# Motor_Test_Bench_ONE_LAYER.net
KiCad netlist of a schematic drawn in EAGLE
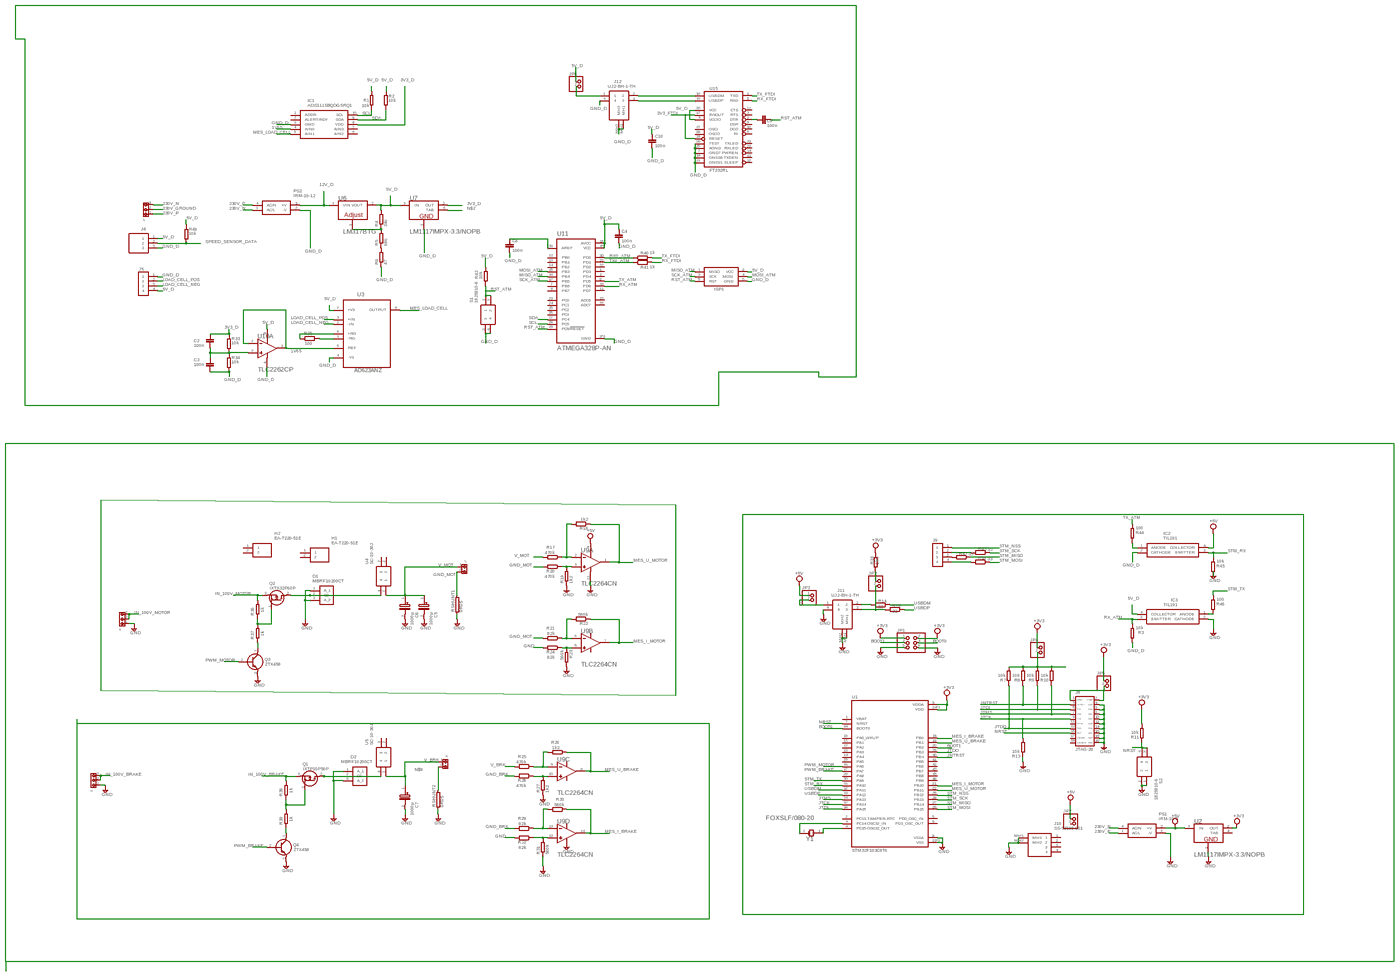
[diagram p0: schematic, sheet 1, overview]
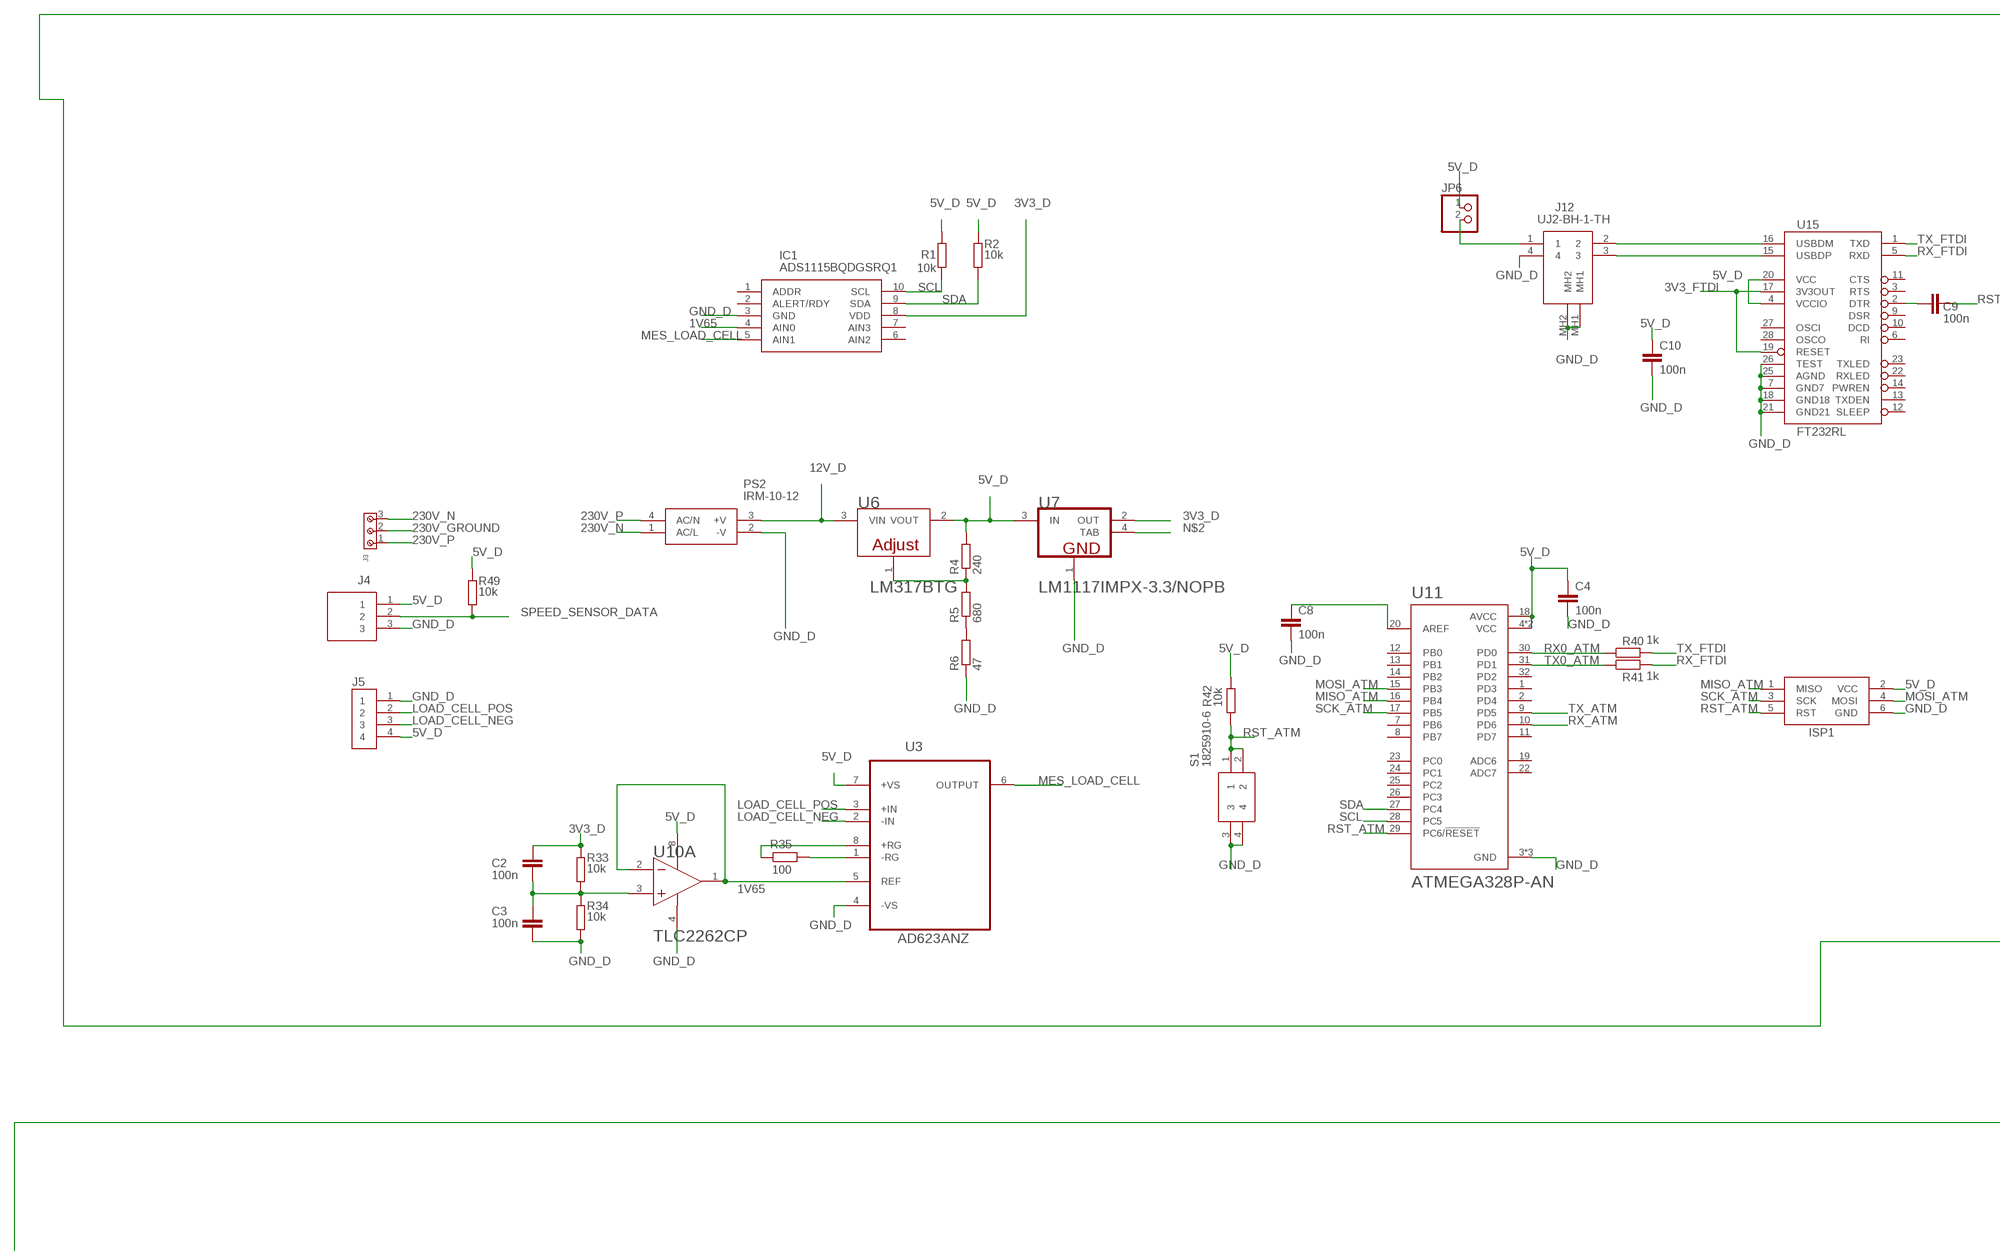
[diagram p1: schematic, sheet 1, part 1 of 4]
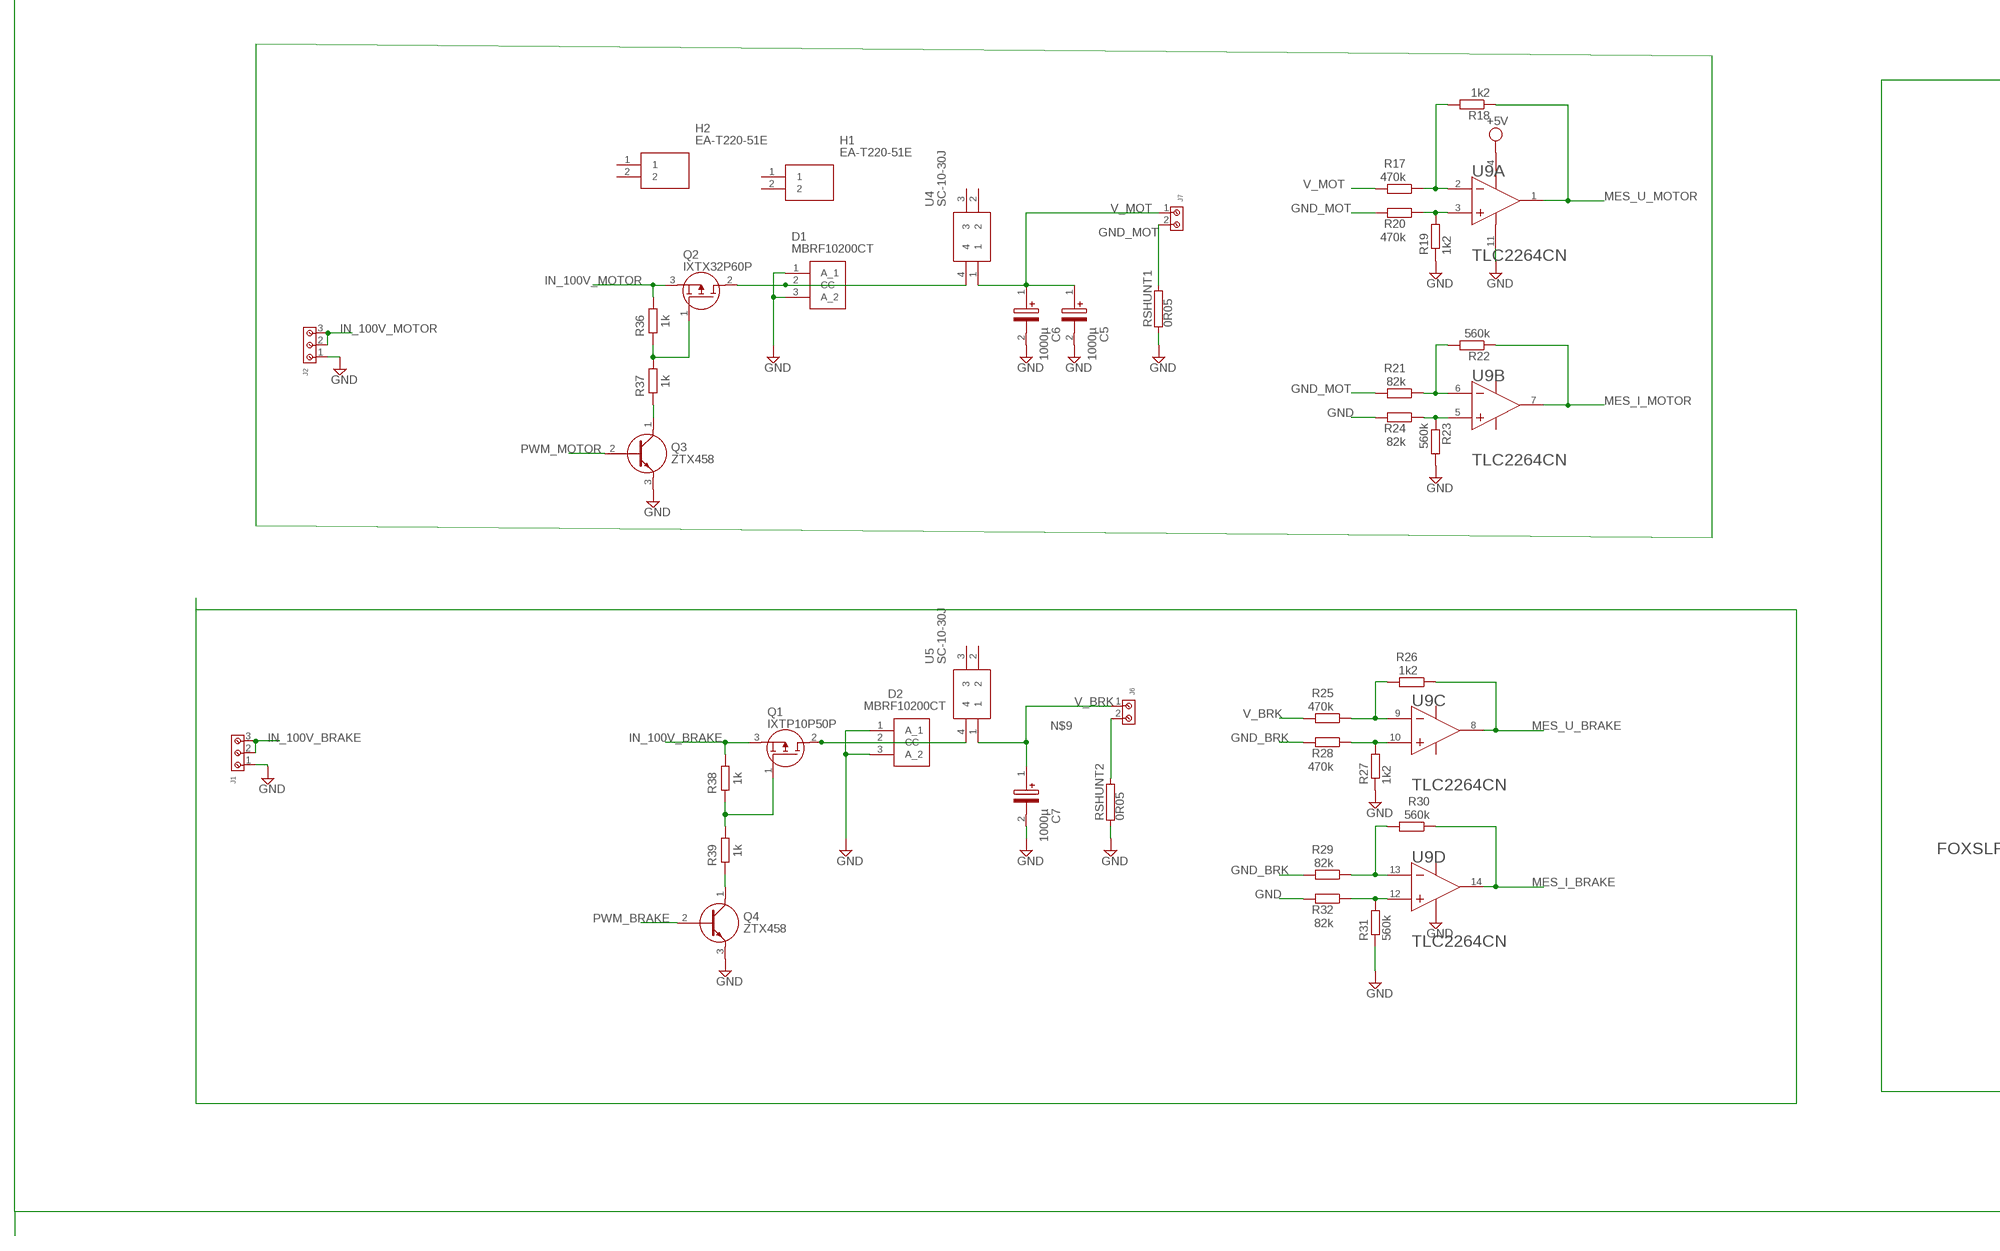
[diagram p2: schematic, sheet 1, part 2 of 4]
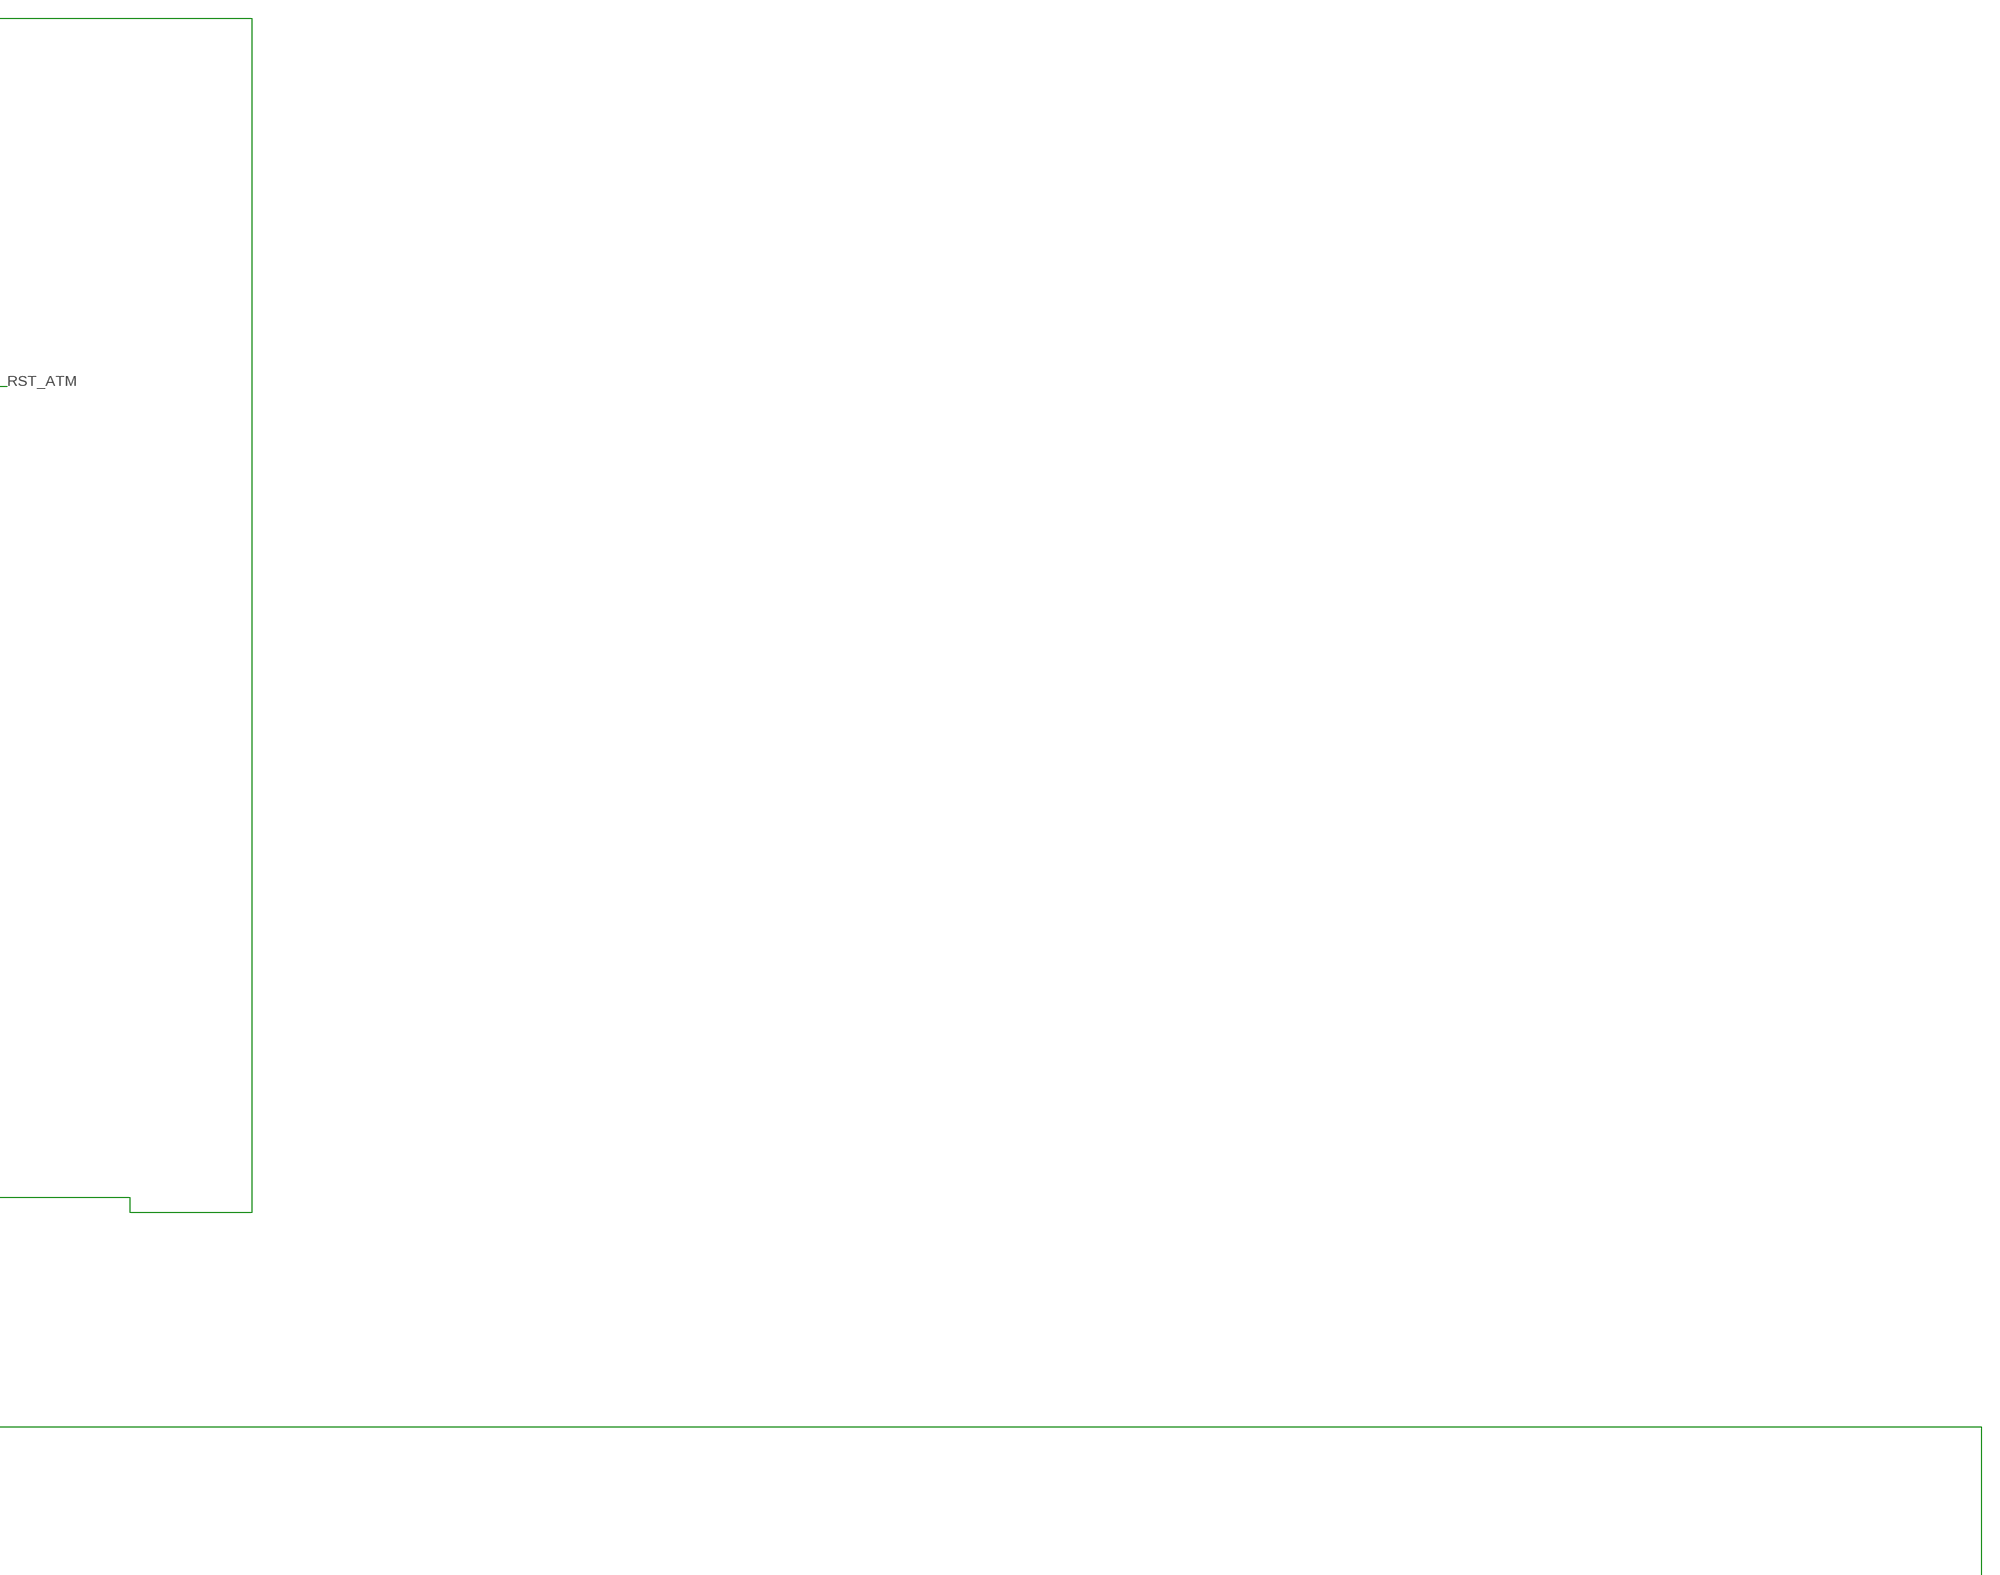
[diagram p3: schematic, sheet 1, part 3 of 4]
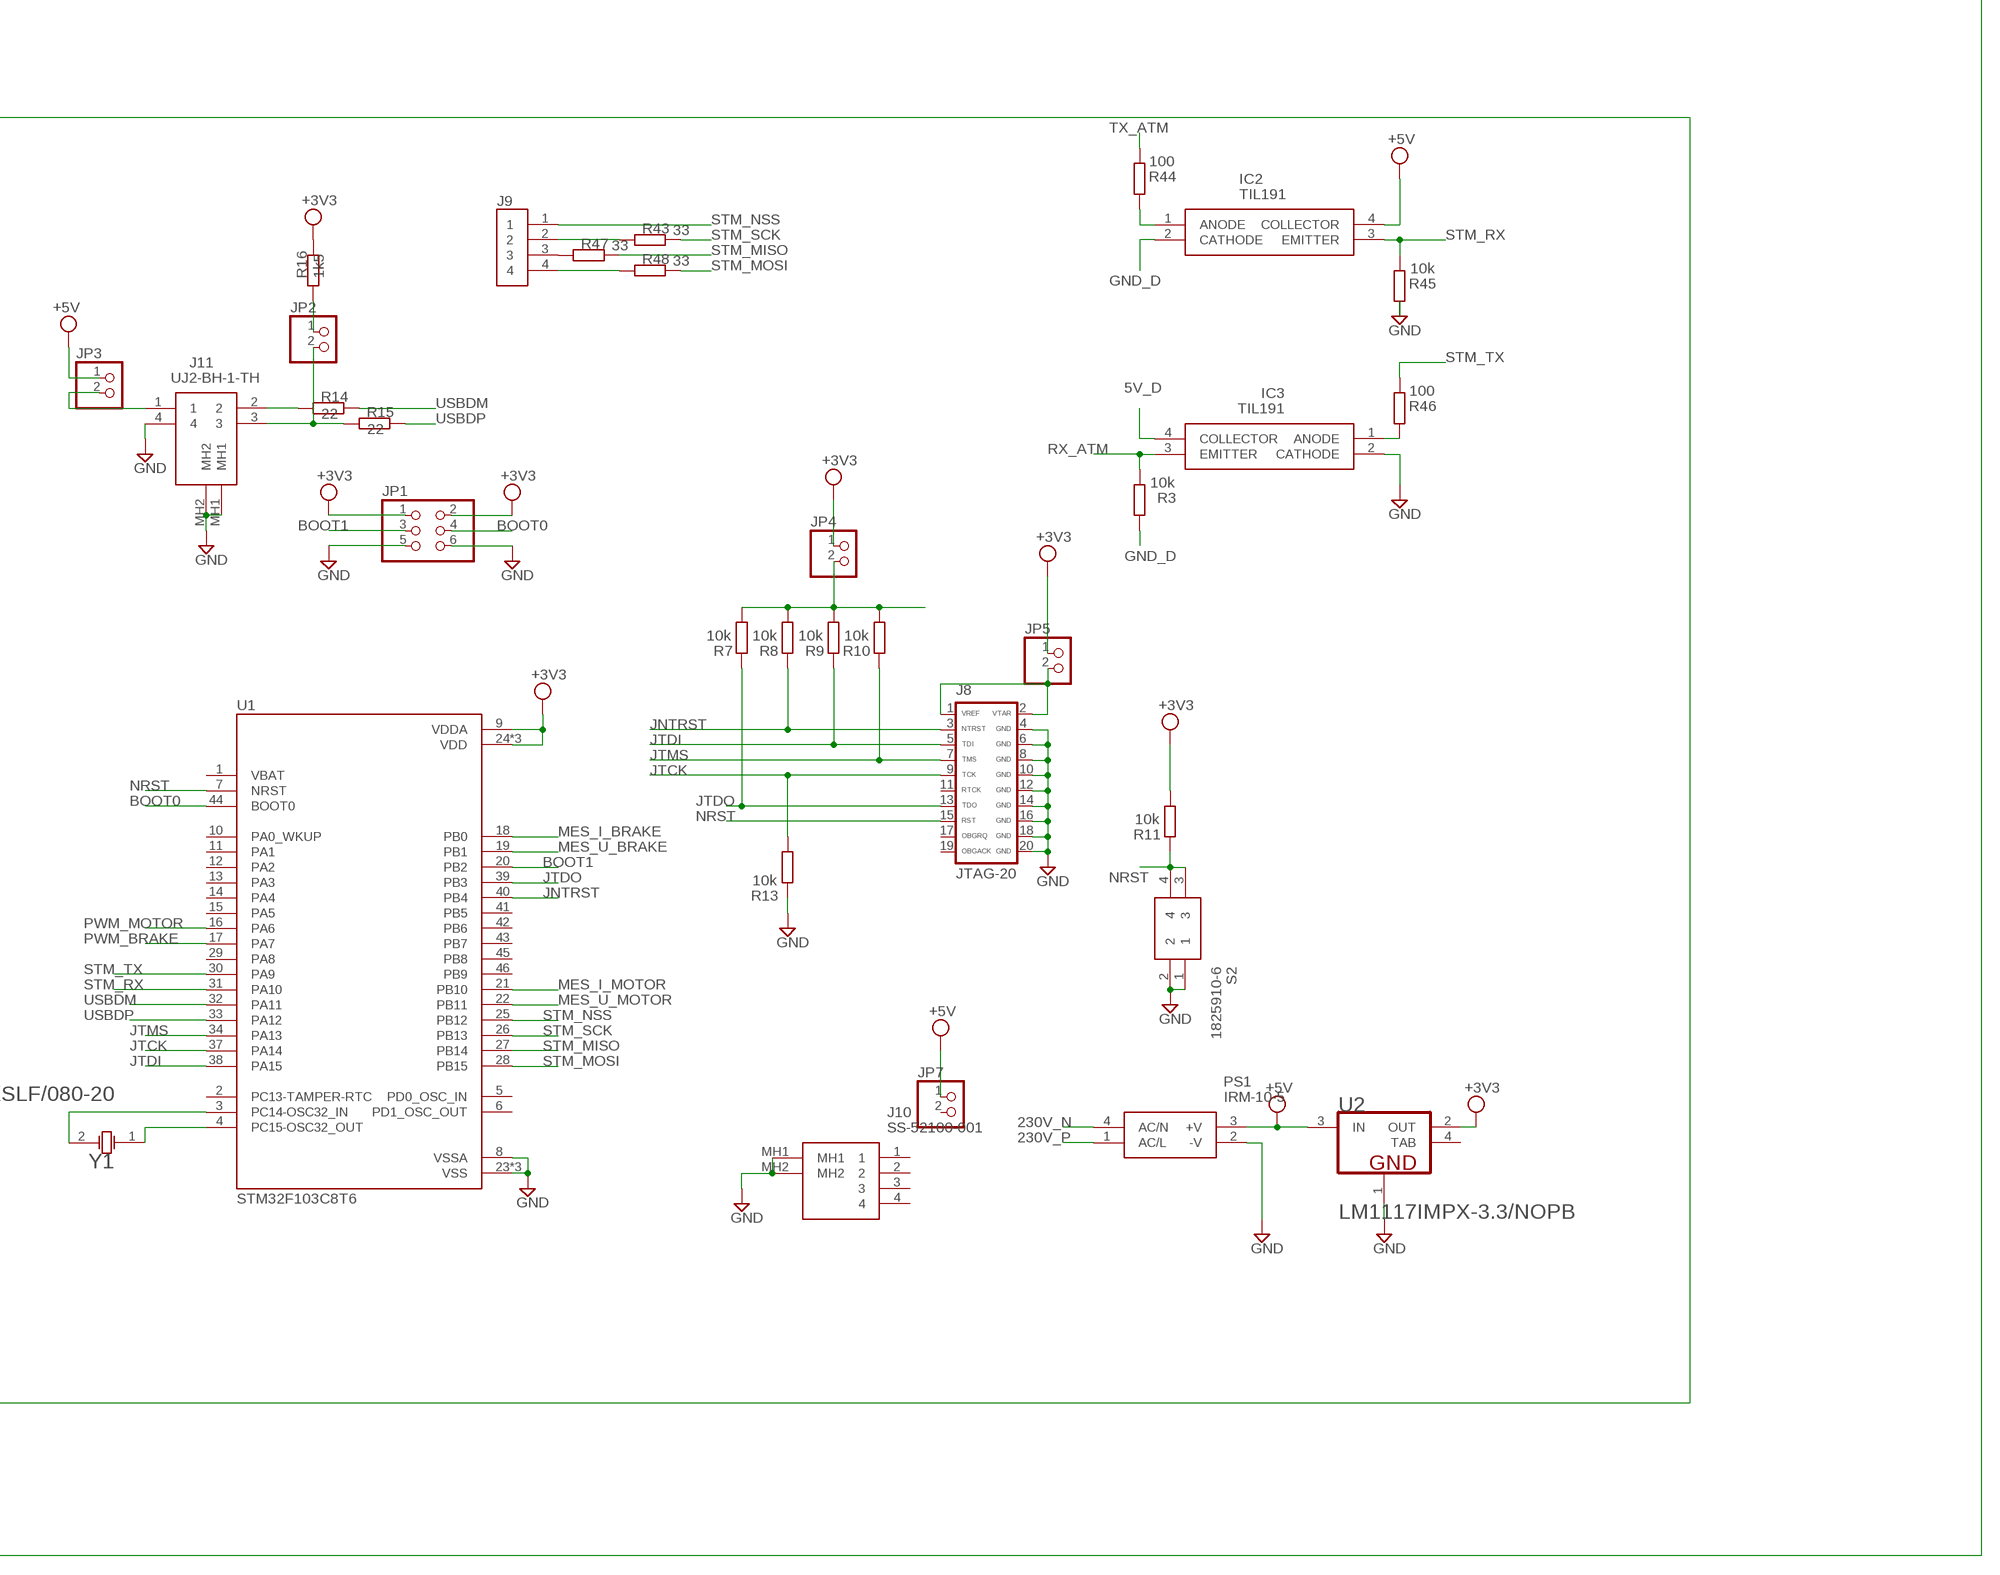
[diagram p4: schematic, sheet 1, part 4 of 4]

(export (version "E")
  (design (tool "Eeschema 10.0.6"))
  (components
    (comp (ref "C2")
      (value "100n")
      (footprint "eagle-import:C0805")
      (libsource (lib "eagle-import") (part "C-EUC0805"))
    )
    (comp (ref "C3")
      (value "100n")
      (footprint "eagle-import:C0805")
      (libsource (lib "eagle-import") (part "C-EUC0805"))
    )
    (comp (ref "C4")
      (value "100n")
      (footprint "eagle-import:CAP_0805")
      (fields
        (field (name "DIGIKEY_PART_NUMBER") "311-1140-2-ND")
        (field (name "MANUFACTURER") "Yageo")
        (field (name "MPN") "CC0805KRX7R9BB104")
        (field (name "CREATED_BY") "PCBLayout.com")
      )
      (libsource (lib "eagle-import") (part "CC0805KRX7R9BB104"))
    )
    (comp (ref "C5")
      (value "1000µ")
      (footprint "eagle-import:SLPX102M200C4P3")
      (fields
        (field (name "MANUFACTURER_PART_NUMBER") "SLPX102M200C4P3")
        (field (name "RS_PART_NUMBER") "7441199P")
      )
      (libsource (lib "eagle-import") (part "SLPX102M200C4P3"))
    )
    (comp (ref "C6")
      (value "1000µ")
      (footprint "eagle-import:SLPX102M200C4P3")
      (fields
        (field (name "MANUFACTURER_PART_NUMBER") "SLPX102M200C4P3")
        (field (name "RS_PART_NUMBER") "7441199P")
      )
      (libsource (lib "eagle-import") (part "SLPX102M200C4P3"))
    )
    (comp (ref "C7")
      (value "1000µ")
      (footprint "eagle-import:SLPX102M200C4P3")
      (fields
        (field (name "MANUFACTURER_PART_NUMBER") "SLPX102M200C4P3")
        (field (name "RS_PART_NUMBER") "7441199P")
      )
      (libsource (lib "eagle-import") (part "SLPX102M200C4P3"))
    )
    (comp (ref "C8")
      (value "100n")
      (footprint "eagle-import:CAP_0805")
      (fields
        (field (name "DIGIKEY_PART_NUMBER") "311-1140-2-ND")
        (field (name "MANUFACTURER") "Yageo")
        (field (name "MPN") "CC0805KRX7R9BB104")
        (field (name "CREATED_BY") "PCBLayout.com")
      )
      (libsource (lib "eagle-import") (part "CC0805KRX7R9BB104"))
    )
    (comp (ref "C9")
      (value "100n")
      (footprint "eagle-import:CAP_0805")
      (fields
        (field (name "DIGIKEY_PART_NUMBER") "311-1140-2-ND")
        (field (name "MANUFACTURER") "Yageo")
        (field (name "MPN") "CC0805KRX7R9BB104")
        (field (name "CREATED_BY") "PCBLayout.com")
      )
      (libsource (lib "eagle-import") (part "CC0805KRX7R9BB104"))
    )
    (comp (ref "C10")
      (value "100n")
      (footprint "eagle-import:CAP_0805")
      (fields
        (field (name "DIGIKEY_PART_NUMBER") "311-1140-2-ND")
        (field (name "MANUFACTURER") "Yageo")
        (field (name "MPN") "CC0805KRX7R9BB104")
        (field (name "CREATED_BY") "PCBLayout.com")
      )
      (libsource (lib "eagle-import") (part "CC0805KRX7R9BB104"))
    )
    (comp (ref "D1")
      (value "MBRF10200CT")
      (footprint "eagle-import:TO254P490X1000X2143-3P")
      (fields (field (name "MOUSER_PART_NUMBER") "621-MBRF10200CT"))
      (libsource (lib "eagle-import") (part "MBRF10200CT"))
    )
    (comp (ref "D2")
      (value "MBRF10200CT")
      (footprint "eagle-import:TO254P490X1000X2143-3P")
      (fields (field (name "MOUSER_PART_NUMBER") "621-MBRF10200CT"))
      (libsource (lib "eagle-import") (part "MBRF10200CT"))
    )
    (comp (ref "H1")
      (value "EA-T220-51E")
      (footprint "eagle-import:EAT22051E")
      (fields (field (name "MOUSER_PART_NUMBER") "588-EA-T220-51E"))
      (libsource (lib "eagle-import") (part "EA-T220-51E"))
    )
    (comp (ref "H2")
      (value "EA-T220-51E")
      (footprint "eagle-import:EAT22051E")
      (fields (field (name "MOUSER_PART_NUMBER") "588-EA-T220-51E"))
      (libsource (lib "eagle-import") (part "EA-T220-51E"))
    )
    (comp (ref "IC1")
      (value "ADS1115BQDGSRQ1")
      (footprint "eagle-import:SOP50P490X110-10N")
      (fields (field (name "MOUSER_PART_NUMBER") "595-ADS1115BQDGSRQ1"))
      (libsource (lib "eagle-import") (part "ADS1115BQDGSRQ1"))
    )
    (comp (ref "IC2")
      (value "TIL191")
      (footprint "eagle-import:DIP762W58P254L450H584Q4N")
      (libsource (lib "eagle-import") (part "TIL191"))
    )
    (comp (ref "IC3")
      (value "TIL191")
      (footprint "eagle-import:DIP762W58P254L450H584Q4N")
      (libsource (lib "eagle-import") (part "TIL191"))
    )
    (comp (ref "ISP1")
      (value "AVRISP-6")
      (footprint "eagle-import:AVRISP")
      (libsource (lib "eagle-import") (part "AVRISP-6"))
    )
    (comp (ref "J1")
      (value "691210910003")
      (footprint "eagle-import:691210910003")
      (libsource (lib "eagle-import") (part "691210910003"))
    )
    (comp (ref "J2")
      (value "691210910003")
      (footprint "eagle-import:691210910003")
      (libsource (lib "eagle-import") (part "691210910003"))
    )
    (comp (ref "J3")
      (value "691210910003")
      (footprint "eagle-import:691210910003")
      (libsource (lib "eagle-import") (part "691210910003"))
    )
    (comp (ref "J4")
      (value "B3B-XH-A(LF)(SN)")
      (footprint "eagle-import:SHDR3W64P0X250_1X3_990X575X700")
      (libsource (lib "eagle-import") (part "B3B-XH-A(LF)(SN)"))
    )
    (comp (ref "J5")
      (value "B4B-XH-A(LF)(SN)")
      (footprint "eagle-import:JST_B4B-XH-A(LF)(SN)")
      (fields (field (name "MF") "JST Sales") (field (name "MP") "B4B-XH-A_LF__SN_"))
      (libsource (lib "eagle-import") (part "B4B-XH-A(LF)(SN)"))
    )
    (comp (ref "J6")
      (value "691210910002")
      (footprint "eagle-import:691210910002")
      (libsource (lib "eagle-import") (part "691210910002"))
    )
    (comp (ref "J7")
      (value "691210910002")
      (footprint "eagle-import:691210910002")
      (libsource (lib "eagle-import") (part "691210910002"))
    )
    (comp (ref "J8")
      (value "JTAG-20")
      (footprint "eagle-import:JTAG-20")
      (libsource (lib "eagle-import") (part "JTAG-20"))
    )
    (comp (ref "J9")
      (value "B4B-XH-A(LF)(SN)")
      (footprint "eagle-import:JST_B4B-XH-A(LF)(SN)")
      (fields (field (name "MF") "JST Sales") (field (name "MP") "B4B-XH-A_LF__SN_"))
      (libsource (lib "eagle-import") (part "B4B-XH-A(LF)(SN)"))
    )
    (comp (ref "J10")
      (value "SS-52100-001")
      (footprint "eagle-import:SS52100001")
      (fields (field (name "MOUSER_PART_NUMBER") "530-SS-52100-001"))
      (libsource (lib "eagle-import") (part "SS-52100-001"))
    )
    (comp (ref "J11")
      (value "UJ2-BH-1-TH")
      (footprint "eagle-import:UJ2BH1TH")
      (fields (field (name "MOUSER_PART_NUMBER") "490-UJ2-BH-1-TH"))
      (libsource (lib "eagle-import") (part "UJ2-BH-1-TH"))
    )
    (comp (ref "J12")
      (value "UJ2-BH-1-TH")
      (footprint "eagle-import:UJ2BH1TH")
      (fields (field (name "MOUSER_PART_NUMBER") "490-UJ2-BH-1-TH"))
      (libsource (lib "eagle-import") (part "UJ2-BH-1-TH"))
    )
    (comp (ref "JP1")
      (value "PINHD-2X3")
      (footprint "eagle-import:2X03")
      (libsource (lib "eagle-import") (part "PINHD-2X3"))
    )
    (comp (ref "JP2")
      (value "PINHD-1X2")
      (footprint "eagle-import:1X02")
      (libsource (lib "eagle-import") (part "PINHD-1X2"))
    )
    (comp (ref "JP3")
      (value "PINHD-1X2")
      (footprint "eagle-import:1X02")
      (libsource (lib "eagle-import") (part "PINHD-1X2"))
    )
    (comp (ref "JP4")
      (value "PINHD-1X2")
      (footprint "eagle-import:1X02")
      (libsource (lib "eagle-import") (part "PINHD-1X2"))
    )
    (comp (ref "JP5")
      (value "PINHD-1X2")
      (footprint "eagle-import:1X02")
      (libsource (lib "eagle-import") (part "PINHD-1X2"))
    )
    (comp (ref "JP6")
      (value "PINHD-1X2")
      (footprint "eagle-import:1X02")
      (libsource (lib "eagle-import") (part "PINHD-1X2"))
    )
    (comp (ref "JP7")
      (value "PINHD-1X2")
      (footprint "eagle-import:1X02")
      (libsource (lib "eagle-import") (part "PINHD-1X2"))
    )
    (comp (ref "PS1")
      (value "IRM-10-5")
      (footprint "eagle-import:IRM-10")
      (fields (field (name "RS_PART_NUMBER") "1358929"))
      (libsource (lib "eagle-import") (part "IRM-10-5"))
    )
    (comp (ref "PS2")
      (value "IRM-10-12")
      (footprint "eagle-import:IRM-10")
      (fields (field (name "RS_PART_NUMBER") "1358930"))
      (libsource (lib "eagle-import") (part "IRM-10-12"))
    )
    (comp (ref "Q1")
      (value "IXTP10P50P")
      (footprint "eagle-import:TO254P483X1028X1700-3P")
      (fields (field (name "MOUSER_PART_NUMBER") "747-IXTP10P50P"))
      (libsource (lib "eagle-import") (part "IXTP10P50P"))
    )
    (comp (ref "Q2")
      (value "IXTX32P60P")
      (footprint "eagle-import:TO545P521X1594X2566-3P")
      (fields (field (name "MOUSER_PART_NUMBER") "747-IXTX32P60P"))
      (libsource (lib "eagle-import") (part "IXTX32P60P"))
    )
    (comp (ref "Q3")
      (value "ZTX458")
      (footprint "eagle-import:ZTX458")
      (fields (field (name "MOUSER_PART_NUMBER") "522-ZTX458"))
      (libsource (lib "eagle-import") (part "ZTX458"))
    )
    (comp (ref "Q4")
      (value "ZTX458")
      (footprint "eagle-import:ZTX458")
      (fields (field (name "MOUSER_PART_NUMBER") "522-ZTX458"))
      (libsource (lib "eagle-import") (part "ZTX458"))
    )
    (comp (ref "R1")
      (value "10k")
      (footprint "eagle-import:R0805")
      (libsource (lib "eagle-import") (part "R-EU_R0805"))
    )
    (comp (ref "R2")
      (value "10k")
      (footprint "eagle-import:R0805")
      (libsource (lib "eagle-import") (part "R-EU_R0805"))
    )
    (comp (ref "R3")
      (value "10k")
      (footprint "eagle-import:R0805")
      (libsource (lib "eagle-import") (part "R-EU_R0805"))
    )
    (comp (ref "R4")
      (value "240")
      (footprint "eagle-import:R0805")
      (libsource (lib "eagle-import") (part "R-EU_R0805"))
    )
    (comp (ref "R5")
      (value "680")
      (footprint "eagle-import:R0805")
      (libsource (lib "eagle-import") (part "R-EU_R0805"))
    )
    (comp (ref "R6")
      (value "47")
      (footprint "eagle-import:R0805")
      (libsource (lib "eagle-import") (part "R-EU_R0805"))
    )
    (comp (ref "R7")
      (value "10k")
      (footprint "eagle-import:R0805")
      (libsource (lib "eagle-import") (part "R-EU_R0805"))
    )
    (comp (ref "R8")
      (value "10k")
      (footprint "eagle-import:R0805")
      (libsource (lib "eagle-import") (part "R-EU_R0805"))
    )
    (comp (ref "R9")
      (value "10k")
      (footprint "eagle-import:R0805")
      (libsource (lib "eagle-import") (part "R-EU_R0805"))
    )
    (comp (ref "R10")
      (value "10k")
      (footprint "eagle-import:R0805")
      (libsource (lib "eagle-import") (part "R-EU_R0805"))
    )
    (comp (ref "R11")
      (value "10k")
      (footprint "eagle-import:R0805")
      (libsource (lib "eagle-import") (part "R-EU_R0805"))
    )
    (comp (ref "R13")
      (value "10k")
      (footprint "eagle-import:R0805")
      (libsource (lib "eagle-import") (part "R-EU_R0805"))
    )
    (comp (ref "R14")
      (value "22")
      (footprint "eagle-import:R0805")
      (libsource (lib "eagle-import") (part "R-EU_R0805"))
    )
    (comp (ref "R15")
      (value "22")
      (footprint "eagle-import:R0805")
      (libsource (lib "eagle-import") (part "R-EU_R0805"))
    )
    (comp (ref "R16")
      (value "1k5")
      (footprint "eagle-import:R0805")
      (libsource (lib "eagle-import") (part "R-EU_R0805"))
    )
    (comp (ref "R17")
      (value "470k")
      (footprint "eagle-import:R0805")
      (libsource (lib "eagle-import") (part "R-EU_R0805"))
    )
    (comp (ref "R18")
      (value "1k2")
      (footprint "eagle-import:R0805")
      (libsource (lib "eagle-import") (part "R-EU_R0805"))
    )
    (comp (ref "R19")
      (value "1k2")
      (footprint "eagle-import:R0805")
      (libsource (lib "eagle-import") (part "R-EU_R0805"))
    )
    (comp (ref "R20")
      (value "470k")
      (footprint "eagle-import:R0805")
      (libsource (lib "eagle-import") (part "R-EU_R0805"))
    )
    (comp (ref "R21")
      (value "82k")
      (footprint "eagle-import:R0805")
      (libsource (lib "eagle-import") (part "R-EU_R0805"))
    )
    (comp (ref "R22")
      (value "560k")
      (footprint "eagle-import:R0805")
      (libsource (lib "eagle-import") (part "R-EU_R0805"))
    )
    (comp (ref "R23")
      (value "560k")
      (footprint "eagle-import:R0805")
      (libsource (lib "eagle-import") (part "R-EU_R0805"))
    )
    (comp (ref "R24")
      (value "82k")
      (footprint "eagle-import:R0805")
      (libsource (lib "eagle-import") (part "R-EU_R0805"))
    )
    (comp (ref "R25")
      (value "470k")
      (footprint "eagle-import:R0805")
      (libsource (lib "eagle-import") (part "R-EU_R0805"))
    )
    (comp (ref "R26")
      (value "1k2")
      (footprint "eagle-import:R0805")
      (libsource (lib "eagle-import") (part "R-EU_R0805"))
    )
    (comp (ref "R27")
      (value "1k2")
      (footprint "eagle-import:R0805")
      (libsource (lib "eagle-import") (part "R-EU_R0805"))
    )
    (comp (ref "R28")
      (value "470k")
      (footprint "eagle-import:R0805")
      (libsource (lib "eagle-import") (part "R-EU_R0805"))
    )
    (comp (ref "R29")
      (value "82k")
      (footprint "eagle-import:R0805")
      (libsource (lib "eagle-import") (part "R-EU_R0805"))
    )
    (comp (ref "R30")
      (value "560k")
      (footprint "eagle-import:R0805")
      (libsource (lib "eagle-import") (part "R-EU_R0805"))
    )
    (comp (ref "R31")
      (value "560k")
      (footprint "eagle-import:R0805")
      (libsource (lib "eagle-import") (part "R-EU_R0805"))
    )
    (comp (ref "R32")
      (value "82k")
      (footprint "eagle-import:R0805")
      (libsource (lib "eagle-import") (part "R-EU_R0805"))
    )
    (comp (ref "R33")
      (value "10k")
      (footprint "eagle-import:R0805")
      (libsource (lib "eagle-import") (part "R-EU_R0805"))
    )
    (comp (ref "R34")
      (value "10k")
      (footprint "eagle-import:R0805")
      (libsource (lib "eagle-import") (part "R-EU_R0805"))
    )
    (comp (ref "R35")
      (value "100")
      (footprint "eagle-import:R0805")
      (libsource (lib "eagle-import") (part "R-EU_R0805"))
    )
    (comp (ref "R36")
      (value "1k")
      (footprint "eagle-import:R0805")
      (libsource (lib "eagle-import") (part "R-EU_R0805"))
    )
    (comp (ref "R37")
      (value "1k")
      (footprint "eagle-import:R0805")
      (libsource (lib "eagle-import") (part "R-EU_R0805"))
    )
    (comp (ref "R38")
      (value "1k")
      (footprint "eagle-import:R0805")
      (libsource (lib "eagle-import") (part "R-EU_R0805"))
    )
    (comp (ref "R39")
      (value "1k")
      (footprint "eagle-import:R0805")
      (libsource (lib "eagle-import") (part "R-EU_R0805"))
    )
    (comp (ref "R40")
      (value "1k")
      (footprint "eagle-import:R0805")
      (libsource (lib "eagle-import") (part "R-EU_R0805"))
    )
    (comp (ref "R41")
      (value "1k")
      (footprint "eagle-import:R0805")
      (libsource (lib "eagle-import") (part "R-EU_R0805"))
    )
    (comp (ref "R42")
      (value "10k")
      (footprint "eagle-import:R0805")
      (libsource (lib "eagle-import") (part "R-EU_R0805"))
    )
    (comp (ref "R43")
      (value "33")
      (footprint "eagle-import:R0805")
      (libsource (lib "eagle-import") (part "R-EU_R0805"))
    )
    (comp (ref "R44")
      (value "100")
      (footprint "eagle-import:R0805")
      (libsource (lib "eagle-import") (part "R-EU_R0805"))
    )
    (comp (ref "R45")
      (value "10k")
      (footprint "eagle-import:R0805")
      (libsource (lib "eagle-import") (part "R-EU_R0805"))
    )
    (comp (ref "R46")
      (value "100")
      (footprint "eagle-import:R0805")
      (libsource (lib "eagle-import") (part "R-EU_R0805"))
    )
    (comp (ref "R47")
      (value "33")
      (footprint "eagle-import:R0805")
      (libsource (lib "eagle-import") (part "R-EU_R0805"))
    )
    (comp (ref "R48")
      (value "33")
      (footprint "eagle-import:R0805")
      (libsource (lib "eagle-import") (part "R-EU_R0805"))
    )
    (comp (ref "R49")
      (value "10k")
      (footprint "eagle-import:R0805")
      (libsource (lib "eagle-import") (part "R-EU_R0805"))
    )
    (comp (ref "RSHUNT1")
      (value "0R05")
      (footprint "eagle-import:RS05_69-70")
      (libsource (lib "eagle-import") (part "RRS05_69-70"))
    )
    (comp (ref "RSHUNT2")
      (value "0R05")
      (footprint "eagle-import:RS05_69-70")
      (libsource (lib "eagle-import") (part "RRS05_69-70"))
    )
    (comp (ref "S1")
      (value "1825910-6")
      (footprint "eagle-import:1825910-6")
      (libsource (lib "eagle-import") (part "1825910-6"))
    )
    (comp (ref "S2")
      (value "1825910-6")
      (footprint "eagle-import:1825910-6")
      (libsource (lib "eagle-import") (part "1825910-6"))
    )
    (comp (ref "U1")
      (value "STM32F103C8T6")
      (footprint "eagle-import:QFP50P900X900X160-48N")
      (fields (field (name "MF") "STMicroelectronics"))
      (libsource (lib "eagle-import") (part "STM32F103C8T6"))
    )
    (comp (ref "U2")
      (value "NATIONAL_SEMICONDUCTOR_LM1117IMPX-3.3-NOPBNATIONAL_SEMICONDUCTOR_LM1117IMPX-3.3-NOPB_0_2")
      (footprint "eagle-import:NATIONAL_SEMICONDUCTOR_LM1117IMPX-3.3-NOPB_2")
      (fields (field (name "MF") "National Semiconductor") (field (name "MPN") "LM1117IMPX-3.3/NOPB"))
      (libsource (lib "eagle-import") (part "NATIONAL_SEMICONDUCTOR_LM1117IMPX-3.3-NOPBNATIONAL_SEMICONDUCTOR_LM1117IMPX-3.3-NOPB_0_2"))
    )
    (comp (ref "U3")
      (value "AD623ANZ")
      (footprint "eagle-import:DIP254P762X533-8")
      (fields (field (name "MF") "Analog Devices"))
      (libsource (lib "eagle-import") (part "AD623ANZ"))
    )
    (comp (ref "U4")
      (value "SC-10-30J")
      (footprint "eagle-import:SC-10-30J")
      (fields (field (name "MOUSER_PART_NUMBER") "80-SC-10-30J") (field (name "RS_PART_NUMBER") "8633778P"))
      (libsource (lib "eagle-import") (part "SC-10-30J"))
    )
    (comp (ref "U5")
      (value "SC-10-30J")
      (footprint "eagle-import:SC-10-30J")
      (fields (field (name "MOUSER_PART_NUMBER") "80-SC-10-30J") (field (name "RS_PART_NUMBER") "8633778P"))
      (libsource (lib "eagle-import") (part "SC-10-30J"))
    )
    (comp (ref "U6")
      (value "ON_SEMI_LM317BTGON_SEMI_LM317BTG_0_0")
      (footprint "eagle-import:ON_SEMI_LM317BTG_0")
      (fields
        (field (name "DIGIKEY_PART_NUMBER") "LM317BTGOS-ND")
        (field (name "MF") "ON Semi")
        (field (name "MOUSER_PART_NUMBER") "863-LM317BTG")
      )
      (libsource (lib "eagle-import") (part "ON_SEMI_LM317BTGON_SEMI_LM317BTG_0_0"))
    )
    (comp (ref "U7")
      (value "NATIONAL_SEMICONDUCTOR_LM1117IMPX-3.3-NOPBNATIONAL_SEMICONDUCTOR_LM1117IMPX-3.3-NOPB_0_2")
      (footprint "eagle-import:NATIONAL_SEMICONDUCTOR_LM1117IMPX-3.3-NOPB_2")
      (fields (field (name "MF") "National Semiconductor") (field (name "MPN") "LM1117IMPX-3.3/NOPB"))
      (libsource (lib "eagle-import") (part "NATIONAL_SEMICONDUCTOR_LM1117IMPX-3.3-NOPBNATIONAL_SEMICONDUCTOR_LM1117IMPX-3.3-NOPB_0_2"))
    )
    (comp (ref "U9")
      (value "TEXAS_INSTRUMENTS_TLC2264CNTEXAS_INSTRUMENTS_TLC2264CN_0_0")
      (footprint "eagle-import:TEXAS_INSTRUMENTS_TLC2264CN_0")
      (fields (field (name "MF") "Texas Instruments") (field (name "MPN") "TLC2264CN"))
      (libsource (lib "eagle-import") (part "TEXAS_INSTRUMENTS_TLC2264CNTEXAS_INSTRUMENTS_TLC2264CN_0_0"))
    )
    (comp (ref "U10")
      (value "TEXAS_INSTRUMENTS_TLC2262CPTEXAS_INSTRUMENTS_TLC2262CP_0_0")
      (footprint "eagle-import:TEXAS_INSTRUMENTS_TLC2262CP_0")
      (fields (field (name "MF") "Texas Instruments") (field (name "MPN") "TLC2262CP"))
      (libsource (lib "eagle-import") (part "TEXAS_INSTRUMENTS_TLC2262CPTEXAS_INSTRUMENTS_TLC2262CP_0_0"))
    )
    (comp (ref "U11")
      (value "ATMEGA328P-AN")
      (footprint "eagle-import:QFP80P900X900X120-32N")
      (fields (field (name "MF") "Microchip"))
      (libsource (lib "eagle-import") (part "ATMEGA328P-AN"))
    )
    (comp (ref "U15")
      (value "FT232RL")
      (footprint "eagle-import:SSOP28DB")
      (libsource (lib "eagle-import") (part "FT232RLSSOP"))
    )
    (comp (ref "Y1")
      (value "FOX_ELECTRONICS_FOXSLF-080-20FOX_ELECTRONICS_FOXSLF-080-20_0_0")
      (footprint "eagle-import:FOX_ELECTRONICS_FOXSLF-080-20_0")
      (fields (field (name "MF") "Fox Electronics") (field (name "MPN") "FOXSLF/080-20"))
      (libsource (lib "eagle-import") (part "FOX_ELECTRONICS_FOXSLF-080-20FOX_ELECTRONICS_FOXSLF-080-20_0_0"))
    )
  )
  (nets
    (net (code "1") (name "+3V3") (class "Default")
      (node (ref "JP1") (pin "1") (pinfunction "1_1") (pintype "passive"))
      (node (ref "JP1") (pin "2") (pinfunction "2_2") (pintype "passive"))
      (node (ref "JP4") (pin "1") (pinfunction "1_1") (pintype "passive"))
      (node (ref "JP5") (pin "1") (pinfunction "1_1") (pintype "passive"))
      (node (ref "R11") (pin "2") (pinfunction "2_2") (pintype "passive"))
      (node (ref "R16") (pin "1") (pinfunction "1_1") (pintype "passive"))
      (node (ref "U1") (pin "24") (pinfunction "VDD_24") (pintype "power_in"))
      (node (ref "U1") (pin "36") (pinfunction "VDD_36") (pintype "power_in"))
      (node (ref "U1") (pin "48") (pinfunction "VDD_48") (pintype "power_in"))
      (node (ref "U1") (pin "9") (pinfunction "VDDA_9") (pintype "power_in"))
      (node (ref "U2") (pin "2") (pinfunction "OUT_2") (pintype "power_in"))
    )
    (net (code "2") (name "+5V") (class "Default")
      (node (ref "IC2") (pin "4") (pinfunction "COLLECTOR_4") (pintype "bidirectional"))
      (node (ref "JP3") (pin "1") (pinfunction "1_1") (pintype "passive"))
      (node (ref "JP7") (pin "1") (pinfunction "1_1") (pintype "passive"))
      (node (ref "PS1") (pin "3") (pinfunction "+V_3") (pintype "bidirectional"))
      (node (ref "U2") (pin "3") (pinfunction "IN_3") (pintype "power_in"))
      (node (ref "U9") (pin "4") (pinfunction "VDD+_4") (pintype "power_in"))
    )
    (net (code "3") (name "/1V65") (class "Default")
      (node (ref "IC1") (pin "4") (pinfunction "AIN0_4") (pintype "bidirectional"))
      (node (ref "U10") (pin "1") (pinfunction "OUT1_1") (pintype "output"))
      (node (ref "U10") (pin "2") (pinfunction "IN1-_2") (pintype "input"))
      (node (ref "U3") (pin "5") (pinfunction "REF_5") (pintype "passive"))
    )
    (net (code "4") (name "/3V3_D") (class "Default")
      (node (ref "C2") (pin "1") (pinfunction "1_1") (pintype "passive"))
      (node (ref "IC1") (pin "8") (pinfunction "VDD_8") (pintype "bidirectional"))
      (node (ref "R33") (pin "1") (pinfunction "1_1") (pintype "passive"))
      (node (ref "U7") (pin "2") (pinfunction "OUT_2") (pintype "power_in"))
    )
    (net (code "5") (name "/3V3_FTDI") (class "Default")
      (node (ref "U15") (pin "17") (pinfunction "3V3OUT_17") (pintype "output"))
      (node (ref "U15") (pin "19") (pinfunction "RESET_19") (pintype "input"))
    )
    (net (code "6") (name "/5V_D") (class "Default")
      (node (ref "C10") (pin "1") (pinfunction "1_1") (pintype "passive"))
      (node (ref "C4") (pin "1") (pinfunction "1_1") (pintype "passive"))
      (node (ref "IC3") (pin "4") (pinfunction "COLLECTOR_4") (pintype "bidirectional"))
      (node (ref "ISP1") (pin "2") (pinfunction "VCC_2") (pintype "power_in"))
      (node (ref "J4") (pin "1") (pinfunction "1_1") (pintype "bidirectional"))
      (node (ref "J5") (pin "4") (pinfunction "4_4") (pintype "passive"))
      (node (ref "JP6") (pin "1") (pinfunction "1_1") (pintype "passive"))
      (node (ref "R1") (pin "2") (pinfunction "2_2") (pintype "passive"))
      (node (ref "R2") (pin "2") (pinfunction "2_2") (pintype "passive"))
      (node (ref "R4") (pin "2") (pinfunction "2_2") (pintype "passive"))
      (node (ref "R42") (pin "2") (pinfunction "2_2") (pintype "passive"))
      (node (ref "R49") (pin "1") (pinfunction "1_1") (pintype "passive"))
      (node (ref "U10") (pin "8") (pinfunction "VDD+_8") (pintype "power_in"))
      (node (ref "U11") (pin "18") (pinfunction "AVCC_18") (pintype "power_in"))
      (node (ref "U11") (pin "4") (pinfunction "VCC_4") (pintype "power_in"))
      (node (ref "U11") (pin "6") (pinfunction "VCC_6") (pintype "power_in"))
      (node (ref "U15") (pin "20") (pinfunction "VCC_20") (pintype "power_in"))
      (node (ref "U15") (pin "4") (pinfunction "VCCIO_4") (pintype "power_in"))
      (node (ref "U3") (pin "7") (pinfunction "+VS_7") (pintype "power_in"))
      (node (ref "U6") (pin "2") (pinfunction "VOUT_2") (pintype "output"))
      (node (ref "U7") (pin "3") (pinfunction "IN_3") (pintype "power_in"))
    )
    (net (code "7") (name "/12V_D") (class "Default")
      (node (ref "PS2") (pin "3") (pinfunction "+V_3") (pintype "bidirectional"))
      (node (ref "U6") (pin "3") (pinfunction "VIN_3") (pintype "input"))
    )
    (net (code "8") (name "/230V_GROUND") (class "Default")
      (node (ref "J3") (pin "2") (pinfunction "2_2") (pintype "passive"))
    )
    (net (code "9") (name "/230V_N") (class "Default")
      (node (ref "J3") (pin "3") (pinfunction "3_3") (pintype "passive"))
      (node (ref "PS1") (pin "4") (pinfunction "AC/N_4") (pintype "bidirectional"))
      (node (ref "PS2") (pin "1") (pinfunction "AC/L_1") (pintype "bidirectional"))
    )
    (net (code "10") (name "/230V_P") (class "Default")
      (node (ref "J3") (pin "1") (pinfunction "1_1") (pintype "passive"))
      (node (ref "PS1") (pin "1") (pinfunction "AC/L_1") (pintype "bidirectional"))
      (node (ref "PS2") (pin "4") (pinfunction "AC/N_4") (pintype "bidirectional"))
    )
    (net (code "11") (name "/BOOT0") (class "Default")
      (node (ref "JP1") (pin "4") (pinfunction "4_4") (pintype "passive"))
      (node (ref "U1") (pin "44") (pinfunction "BOOT0_44") (pintype "input"))
    )
    (net (code "12") (name "/BOOT1") (class "Default")
      (node (ref "JP1") (pin "3") (pinfunction "3_3") (pintype "passive"))
      (node (ref "U1") (pin "20") (pinfunction "PB2_20") (pintype "bidirectional"))
    )
    (net (code "13") (name "/GND_BRK") (class "Default")
      (node (ref "R28") (pin "2") (pinfunction "2_2") (pintype "passive"))
      (node (ref "R29") (pin "2") (pinfunction "2_2") (pintype "passive"))
    )
    (net (code "14") (name "/GND_D") (class "Default")
      (node (ref "C10") (pin "2") (pinfunction "2_2") (pintype "passive"))
      (node (ref "C3") (pin "2") (pinfunction "2_2") (pintype "passive"))
      (node (ref "C4") (pin "2") (pinfunction "2_2") (pintype "passive"))
      (node (ref "C8") (pin "2") (pinfunction "2_2") (pintype "passive"))
      (node (ref "IC1") (pin "3") (pinfunction "GND_3") (pintype "bidirectional"))
      (node (ref "IC2") (pin "2") (pinfunction "CATHODE_2") (pintype "bidirectional"))
      (node (ref "ISP1") (pin "6") (pinfunction "GND_6") (pintype "power_in"))
      (node (ref "J12") (pin "4") (pinfunction "4_4") (pintype "bidirectional"))
      (node (ref "J12") (pin "MH1") (pinfunction "MH1_MH1") (pintype "bidirectional"))
      (node (ref "J12") (pin "MH2") (pinfunction "MH2_MH2") (pintype "bidirectional"))
      (node (ref "J4") (pin "3") (pinfunction "3_3") (pintype "bidirectional"))
      (node (ref "J5") (pin "1") (pinfunction "1_1") (pintype "passive"))
      (node (ref "PS2") (pin "2") (pinfunction "-V_2") (pintype "bidirectional"))
      (node (ref "R3") (pin "1") (pinfunction "1_1") (pintype "passive"))
      (node (ref "R34") (pin "2") (pinfunction "2_2") (pintype "passive"))
      (node (ref "R6") (pin "1") (pinfunction "1_1") (pintype "passive"))
      (node (ref "S1") (pin "3") (pinfunction "3_3") (pintype "bidirectional"))
      (node (ref "S1") (pin "4") (pinfunction "4_4") (pintype "bidirectional"))
      (node (ref "U10") (pin "4") (pinfunction "VDD-/GND_4") (pintype "power_in"))
      (node (ref "U11") (pin "21") (pinfunction "GND_21") (pintype "power_in"))
      (node (ref "U11") (pin "3") (pinfunction "GND_3") (pintype "power_in"))
      (node (ref "U11") (pin "5") (pinfunction "GND_5") (pintype "power_in"))
      (node (ref "U15") (pin "18") (pinfunction "GND18_18") (pintype "power_in"))
      (node (ref "U15") (pin "21") (pinfunction "GND21_21") (pintype "power_in"))
      (node (ref "U15") (pin "25") (pinfunction "AGND_25") (pintype "power_in"))
      (node (ref "U15") (pin "26") (pinfunction "TEST_26") (pintype "input"))
      (node (ref "U15") (pin "7") (pinfunction "GND7_7") (pintype "power_in"))
      (node (ref "U3") (pin "4") (pinfunction "-VS_4") (pintype "power_in"))
      (node (ref "U7") (pin "1") (pinfunction "GND_1") (pintype "power_in"))
    )
    (net (code "15") (name "/GND_MOT") (class "Default")
      (node (ref "J7") (pin "2") (pinfunction "2_2") (pintype "passive"))
      (node (ref "R20") (pin "2") (pinfunction "2_2") (pintype "passive"))
      (node (ref "R21") (pin "2") (pinfunction "2_2") (pintype "passive"))
      (node (ref "RSHUNT1") (pin "2") (pinfunction "2_2") (pintype "passive"))
    )
    (net (code "16") (name "/IN_100V_BRAKE") (class "Default")
      (node (ref "J1") (pin "2") (pinfunction "2_2") (pintype "passive"))
      (node (ref "J1") (pin "3") (pinfunction "3_3") (pintype "passive"))
      (node (ref "Q1") (pin "3") (pinfunction "S_3") (pintype "bidirectional"))
      (node (ref "R38") (pin "2") (pinfunction "2_2") (pintype "passive"))
    )
    (net (code "17") (name "/IN_100V_MOTOR") (class "Default")
      (node (ref "J2") (pin "2") (pinfunction "2_2") (pintype "passive"))
      (node (ref "J2") (pin "3") (pinfunction "3_3") (pintype "passive"))
      (node (ref "Q2") (pin "3") (pinfunction "S_3") (pintype "bidirectional"))
      (node (ref "R36") (pin "2") (pinfunction "2_2") (pintype "passive"))
    )
    (net (code "18") (name "/JNTRST") (class "Default")
      (node (ref "J8") (pin "3") (pinfunction "NTRST_3") (pintype "passive"))
      (node (ref "R8") (pin "1") (pinfunction "1_1") (pintype "passive"))
      (node (ref "U1") (pin "40") (pinfunction "PB4_40") (pintype "bidirectional"))
    )
    (net (code "19") (name "/JTCK") (class "Default")
      (node (ref "J8") (pin "9") (pinfunction "TCK_9") (pintype "passive"))
      (node (ref "R13") (pin "2") (pinfunction "2_2") (pintype "passive"))
      (node (ref "U1") (pin "37") (pinfunction "PA14_37") (pintype "bidirectional"))
    )
    (net (code "20") (name "/JTDI") (class "Default")
      (node (ref "J8") (pin "5") (pinfunction "TDI_5") (pintype "passive"))
      (node (ref "R9") (pin "1") (pinfunction "1_1") (pintype "passive"))
      (node (ref "U1") (pin "38") (pinfunction "PA15_38") (pintype "bidirectional"))
    )
    (net (code "21") (name "/JTDO") (class "Default")
      (node (ref "J8") (pin "13") (pinfunction "TDO_13") (pintype "passive"))
      (node (ref "R7") (pin "1") (pinfunction "1_1") (pintype "passive"))
      (node (ref "U1") (pin "39") (pinfunction "PB3_39") (pintype "bidirectional"))
    )
    (net (code "22") (name "/JTMS") (class "Default")
      (node (ref "J8") (pin "7") (pinfunction "TMS_7") (pintype "passive"))
      (node (ref "R10") (pin "1") (pinfunction "1_1") (pintype "passive"))
      (node (ref "U1") (pin "34") (pinfunction "PA13_34") (pintype "bidirectional"))
    )
    (net (code "23") (name "/LOAD_CELL_NEG") (class "Default")
      (node (ref "J5") (pin "3") (pinfunction "3_3") (pintype "passive"))
      (node (ref "U3") (pin "2") (pinfunction "-IN_2") (pintype "input"))
    )
    (net (code "24") (name "/LOAD_CELL_POS") (class "Default")
      (node (ref "J5") (pin "2") (pinfunction "2_2") (pintype "passive"))
      (node (ref "U3") (pin "3") (pinfunction "+IN_3") (pintype "input"))
    )
    (net (code "25") (name "/MES_I_BRAKE") (class "Default")
      (node (ref "R30") (pin "1") (pinfunction "1_1") (pintype "passive"))
      (node (ref "U1") (pin "18") (pinfunction "PB0_18") (pintype "bidirectional"))
      (node (ref "U9") (pin "14") (pinfunction "OUT4_14") (pintype "output"))
    )
    (net (code "26") (name "/MES_I_MOTOR") (class "Default")
      (node (ref "R22") (pin "1") (pinfunction "1_1") (pintype "passive"))
      (node (ref "U1") (pin "21") (pinfunction "PB10_21") (pintype "bidirectional"))
      (node (ref "U9") (pin "7") (pinfunction "OUT2_7") (pintype "output"))
    )
    (net (code "27") (name "/MES_LOAD_CELL") (class "Default")
      (node (ref "IC1") (pin "5") (pinfunction "AIN1_5") (pintype "bidirectional"))
      (node (ref "U3") (pin "6") (pinfunction "OUTPUT_6") (pintype "output"))
    )
    (net (code "28") (name "/MES_U_BRAKE") (class "Default")
      (node (ref "R26") (pin "1") (pinfunction "1_1") (pintype "passive"))
      (node (ref "U1") (pin "19") (pinfunction "PB1_19") (pintype "bidirectional"))
      (node (ref "U9") (pin "8") (pinfunction "OUT3_8") (pintype "output"))
    )
    (net (code "29") (name "/MES_U_MOTOR") (class "Default")
      (node (ref "R18") (pin "1") (pinfunction "1_1") (pintype "passive"))
      (node (ref "U1") (pin "22") (pinfunction "PB11_22") (pintype "bidirectional"))
      (node (ref "U9") (pin "1") (pinfunction "OUT1_1") (pintype "output"))
    )
    (net (code "30") (name "/MISO_ATM") (class "Default")
      (node (ref "ISP1") (pin "1") (pinfunction "MISO_1") (pintype "input"))
      (node (ref "U11") (pin "16") (pinfunction "PB4_16") (pintype "bidirectional"))
    )
    (net (code "31") (name "/MOSI_ATM") (class "Default")
      (node (ref "ISP1") (pin "4") (pinfunction "MOSI_4") (pintype "output"))
      (node (ref "U11") (pin "15") (pinfunction "PB3_15") (pintype "bidirectional"))
    )
    (net (code "32") (name "/N$2") (class "Default")
      (node (ref "U7") (pin "4") (pinfunction "TAB_4") (pintype "power_in"))
    )
    (net (code "33") (name "/N$9") (class "Default")
      (node (ref "J6") (pin "2") (pinfunction "2_2") (pintype "passive"))
      (node (ref "RSHUNT2") (pin "2") (pinfunction "2_2") (pintype "passive"))
    )
    (net (code "34") (name "/NRST") (class "Default")
      (node (ref "J8") (pin "15") (pinfunction "RST_15") (pintype "passive"))
      (node (ref "R11") (pin "1") (pinfunction "1_1") (pintype "passive"))
      (node (ref "S2") (pin "3") (pinfunction "3_3") (pintype "bidirectional"))
      (node (ref "S2") (pin "4") (pinfunction "4_4") (pintype "bidirectional"))
      (node (ref "U1") (pin "7") (pinfunction "NRST_7") (pintype "input"))
    )
    (net (code "35") (name "/PWM_BRAKE") (class "Default")
      (node (ref "Q4") (pin "2") (pinfunction "B_2") (pintype "bidirectional"))
      (node (ref "U1") (pin "17") (pinfunction "PA7_17") (pintype "bidirectional"))
    )
    (net (code "36") (name "/PWM_MOTOR") (class "Default")
      (node (ref "Q3") (pin "2") (pinfunction "B_2") (pintype "bidirectional"))
      (node (ref "U1") (pin "16") (pinfunction "PA6_16") (pintype "bidirectional"))
    )
    (net (code "37") (name "/RST_ATM") (class "Default")
      (node (ref "C9") (pin "1") (pinfunction "1_1") (pintype "passive"))
      (node (ref "ISP1") (pin "5") (pinfunction "RST_5") (pintype "output"))
      (node (ref "R42") (pin "1") (pinfunction "1_1") (pintype "passive"))
      (node (ref "S1") (pin "1") (pinfunction "1_1") (pintype "bidirectional"))
      (node (ref "S1") (pin "2") (pinfunction "2_2") (pintype "bidirectional"))
      (node (ref "U11") (pin "29") (pinfunction "PC6/~{RESET}_29") (pintype "bidirectional"))
    )
    (net (code "38") (name "/RX0_ATM") (class "Default")
      (node (ref "R40") (pin "1") (pinfunction "1_1") (pintype "passive"))
      (node (ref "U11") (pin "30") (pinfunction "PD0_30") (pintype "bidirectional"))
    )
    (net (code "39") (name "/RX_ATM") (class "Default")
      (node (ref "IC3") (pin "3") (pinfunction "EMITTER_3") (pintype "bidirectional"))
      (node (ref "R3") (pin "2") (pinfunction "2_2") (pintype "passive"))
      (node (ref "U11") (pin "10") (pinfunction "PD6_10") (pintype "bidirectional"))
    )
    (net (code "40") (name "/RX_FTDI") (class "Default")
      (node (ref "R41") (pin "2") (pinfunction "2_2") (pintype "passive"))
      (node (ref "U15") (pin "5") (pinfunction "RXD_5") (pintype "input"))
    )
    (net (code "41") (name "/SCK_ATM") (class "Default")
      (node (ref "ISP1") (pin "3") (pinfunction "SCK_3") (pintype "output"))
      (node (ref "U11") (pin "17") (pinfunction "PB5_17") (pintype "bidirectional"))
    )
    (net (code "42") (name "/SCL") (class "Default")
      (node (ref "IC1") (pin "10") (pinfunction "SCL_10") (pintype "bidirectional"))
      (node (ref "R1") (pin "1") (pinfunction "1_1") (pintype "passive"))
      (node (ref "U11") (pin "28") (pinfunction "PC5_28") (pintype "bidirectional"))
    )
    (net (code "43") (name "/SDA") (class "Default")
      (node (ref "IC1") (pin "9") (pinfunction "SDA_9") (pintype "bidirectional"))
      (node (ref "R2") (pin "1") (pinfunction "1_1") (pintype "passive"))
      (node (ref "U11") (pin "27") (pinfunction "PC4_27") (pintype "bidirectional"))
    )
    (net (code "44") (name "/SPEED_SENSOR_DATA") (class "Default")
      (node (ref "J4") (pin "2") (pinfunction "2_2") (pintype "bidirectional"))
      (node (ref "R49") (pin "2") (pinfunction "2_2") (pintype "passive"))
    )
    (net (code "45") (name "/STM_MISO") (class "Default")
      (node (ref "R47") (pin "1") (pinfunction "1_1") (pintype "passive"))
      (node (ref "U1") (pin "27") (pinfunction "PB14_27") (pintype "bidirectional"))
    )
    (net (code "46") (name "/STM_MOSI") (class "Default")
      (node (ref "R48") (pin "1") (pinfunction "1_1") (pintype "passive"))
      (node (ref "U1") (pin "28") (pinfunction "PB15_28") (pintype "bidirectional"))
    )
    (net (code "47") (name "/STM_NSS") (class "Default")
      (node (ref "J9") (pin "1") (pinfunction "1_1") (pintype "passive"))
      (node (ref "U1") (pin "25") (pinfunction "PB12_25") (pintype "bidirectional"))
    )
    (net (code "48") (name "/STM_RX") (class "Default")
      (node (ref "IC2") (pin "3") (pinfunction "EMITTER_3") (pintype "bidirectional"))
      (node (ref "R45") (pin "2") (pinfunction "2_2") (pintype "passive"))
      (node (ref "U1") (pin "31") (pinfunction "PA10_31") (pintype "bidirectional"))
    )
    (net (code "49") (name "/STM_SCK") (class "Default")
      (node (ref "R43") (pin "1") (pinfunction "1_1") (pintype "passive"))
      (node (ref "U1") (pin "26") (pinfunction "PB13_26") (pintype "bidirectional"))
    )
    (net (code "50") (name "/STM_TX") (class "Default")
      (node (ref "R46") (pin "2") (pinfunction "2_2") (pintype "passive"))
      (node (ref "U1") (pin "30") (pinfunction "PA9_30") (pintype "bidirectional"))
    )
    (net (code "51") (name "/TAB") (class "Default")
      (node (ref "U2") (pin "4") (pinfunction "TAB_4") (pintype "power_in"))
    )
    (net (code "52") (name "/TX0_ATM") (class "Default")
      (node (ref "R41") (pin "1") (pinfunction "1_1") (pintype "passive"))
      (node (ref "U11") (pin "31") (pinfunction "PD1_31") (pintype "bidirectional"))
    )
    (net (code "53") (name "/TX_ATM") (class "Default")
      (node (ref "R44") (pin "2") (pinfunction "2_2") (pintype "passive"))
      (node (ref "U11") (pin "9") (pinfunction "PD5_9") (pintype "bidirectional"))
    )
    (net (code "54") (name "/TX_FTDI") (class "Default")
      (node (ref "R40") (pin "2") (pinfunction "2_2") (pintype "passive"))
      (node (ref "U15") (pin "1") (pinfunction "TXD_1") (pintype "output"))
    )
    (net (code "55") (name "/USBDM") (class "Default")
      (node (ref "R14") (pin "1") (pinfunction "1_1") (pintype "passive"))
      (node (ref "U1") (pin "32") (pinfunction "PA11_32") (pintype "bidirectional"))
    )
    (net (code "56") (name "/USBDP") (class "Default")
      (node (ref "R15") (pin "1") (pinfunction "1_1") (pintype "passive"))
      (node (ref "U1") (pin "33") (pinfunction "PA12_33") (pintype "bidirectional"))
    )
    (net (code "57") (name "/V_BRK") (class "Default")
      (node (ref "C7") (pin "1") (pinfunction "+_1") (pintype "bidirectional"))
      (node (ref "J6") (pin "1") (pinfunction "1_1") (pintype "passive"))
      (node (ref "R25") (pin "2") (pinfunction "2_2") (pintype "passive"))
      (node (ref "U5") (pin "1") (pinfunction "1_1") (pintype "bidirectional"))
    )
    (net (code "58") (name "/V_MOT") (class "Default")
      (node (ref "C5") (pin "1") (pinfunction "+_1") (pintype "bidirectional"))
      (node (ref "C6") (pin "1") (pinfunction "+_1") (pintype "bidirectional"))
      (node (ref "J7") (pin "1") (pinfunction "1_1") (pintype "passive"))
      (node (ref "R17") (pin "2") (pinfunction "2_2") (pintype "passive"))
      (node (ref "U4") (pin "1") (pinfunction "1_1") (pintype "bidirectional"))
    )
    (net (code "59") (name "GND") (class "Default")
      (node (ref "C5") (pin "2") (pinfunction "-_2") (pintype "bidirectional"))
      (node (ref "C6") (pin "2") (pinfunction "-_2") (pintype "bidirectional"))
      (node (ref "C7") (pin "2") (pinfunction "-_2") (pintype "bidirectional"))
      (node (ref "D1") (pin "1") (pinfunction "A_1_1") (pintype "bidirectional"))
      (node (ref "D1") (pin "3") (pinfunction "A_2_3") (pintype "bidirectional"))
      (node (ref "D2") (pin "1") (pinfunction "A_1_1") (pintype "bidirectional"))
      (node (ref "D2") (pin "3") (pinfunction "A_2_3") (pintype "bidirectional"))
      (node (ref "IC3") (pin "2") (pinfunction "CATHODE_2") (pintype "bidirectional"))
      (node (ref "J1") (pin "1") (pinfunction "1_1") (pintype "passive"))
      (node (ref "J10") (pin "MH1") (pinfunction "MH1_MH1") (pintype "bidirectional"))
      (node (ref "J10") (pin "MH2") (pinfunction "MH2_MH2") (pintype "bidirectional"))
      (node (ref "J11") (pin "4") (pinfunction "4_4") (pintype "bidirectional"))
      (node (ref "J11") (pin "MH1") (pinfunction "MH1_MH1") (pintype "bidirectional"))
      (node (ref "J11") (pin "MH2") (pinfunction "MH2_MH2") (pintype "bidirectional"))
      (node (ref "J2") (pin "1") (pinfunction "1_1") (pintype "passive"))
      (node (ref "J8") (pin "10") (pinfunction "GND_10") (pintype "passive"))
      (node (ref "J8") (pin "12") (pinfunction "GND_12") (pintype "passive"))
      (node (ref "J8") (pin "14") (pinfunction "GND_14") (pintype "passive"))
      (node (ref "J8") (pin "16") (pinfunction "GND_16") (pintype "passive"))
      (node (ref "J8") (pin "18") (pinfunction "GND_18") (pintype "passive"))
      (node (ref "J8") (pin "20") (pinfunction "GND_20") (pintype "passive"))
      (node (ref "J8") (pin "4") (pinfunction "GND_4") (pintype "passive"))
      (node (ref "J8") (pin "6") (pinfunction "GND_6") (pintype "passive"))
      (node (ref "J8") (pin "8") (pinfunction "GND_8") (pintype "passive"))
      (node (ref "JP1") (pin "5") (pinfunction "5_5") (pintype "passive"))
      (node (ref "JP1") (pin "6") (pinfunction "6_6") (pintype "passive"))
      (node (ref "PS1") (pin "2") (pinfunction "-V_2") (pintype "bidirectional"))
      (node (ref "Q3") (pin "3") (pinfunction "C_3") (pintype "bidirectional"))
      (node (ref "Q4") (pin "3") (pinfunction "C_3") (pintype "bidirectional"))
      (node (ref "R13") (pin "1") (pinfunction "1_1") (pintype "passive"))
      (node (ref "R19") (pin "1") (pinfunction "1_1") (pintype "passive"))
      (node (ref "R23") (pin "2") (pinfunction "2_2") (pintype "passive"))
      (node (ref "R24") (pin "2") (pinfunction "2_2") (pintype "passive"))
      (node (ref "R27") (pin "1") (pinfunction "1_1") (pintype "passive"))
      (node (ref "R31") (pin "1") (pinfunction "1_1") (pintype "passive"))
      (node (ref "R32") (pin "2") (pinfunction "2_2") (pintype "passive"))
      (node (ref "R45") (pin "1") (pinfunction "1_1") (pintype "passive"))
      (node (ref "RSHUNT1") (pin "1") (pinfunction "1_1") (pintype "passive"))
      (node (ref "RSHUNT2") (pin "1") (pinfunction "1_1") (pintype "passive"))
      (node (ref "S2") (pin "1") (pinfunction "1_1") (pintype "bidirectional"))
      (node (ref "S2") (pin "2") (pinfunction "2_2") (pintype "bidirectional"))
      (node (ref "U1") (pin "23") (pinfunction "VSS_23") (pintype "power_in"))
      (node (ref "U1") (pin "35") (pinfunction "VSS_35") (pintype "power_in"))
      (node (ref "U1") (pin "47") (pinfunction "VSS_47") (pintype "power_in"))
      (node (ref "U1") (pin "8") (pinfunction "VSSA_8") (pintype "power_in"))
      (node (ref "U2") (pin "1") (pinfunction "GND_1") (pintype "power_in"))
      (node (ref "U9") (pin "11") (pinfunction "VDD-/GND_11") (pintype "power_in"))
    )
    (net (code "60") (name "Net-(D1-CC)") (class "Default")
      (node (ref "D1") (pin "2") (pinfunction "CC_2") (pintype "bidirectional"))
      (node (ref "Q2") (pin "2") (pinfunction "D_2") (pintype "bidirectional"))
      (node (ref "U4") (pin "4") (pinfunction "4_4") (pintype "bidirectional"))
    )
    (net (code "61") (name "Net-(D2-CC)") (class "Default")
      (node (ref "D2") (pin "2") (pinfunction "CC_2") (pintype "bidirectional"))
      (node (ref "Q1") (pin "2") (pinfunction "D_2") (pintype "bidirectional"))
      (node (ref "U5") (pin "4") (pinfunction "4_4") (pintype "bidirectional"))
    )
    (net (code "62") (name "Net-(IC2-ANODE)") (class "Default")
      (node (ref "IC2") (pin "1") (pinfunction "ANODE_1") (pintype "bidirectional"))
      (node (ref "R44") (pin "1") (pinfunction "1_1") (pintype "passive"))
    )
    (net (code "63") (name "Net-(IC3-ANODE)") (class "Default")
      (node (ref "IC3") (pin "1") (pinfunction "ANODE_1") (pintype "bidirectional"))
      (node (ref "R46") (pin "1") (pinfunction "1_1") (pintype "passive"))
    )
    (net (code "64") (name "Net-(J8-VREF)") (class "Default")
      (node (ref "J8") (pin "1") (pinfunction "VREF_1") (pintype "passive"))
      (node (ref "J8") (pin "2") (pinfunction "VTAR_2") (pintype "passive"))
      (node (ref "JP5") (pin "2") (pinfunction "2_2") (pintype "passive"))
    )
    (net (code "65") (name "Net-(J9-Pad2)") (class "Default")
      (node (ref "J9") (pin "2") (pinfunction "2_2") (pintype "passive"))
      (node (ref "R43") (pin "2") (pinfunction "2_2") (pintype "passive"))
    )
    (net (code "66") (name "Net-(J9-Pad3)") (class "Default")
      (node (ref "J9") (pin "3") (pinfunction "3_3") (pintype "passive"))
      (node (ref "R47") (pin "2") (pinfunction "2_2") (pintype "passive"))
    )
    (net (code "67") (name "Net-(J9-Pad4)") (class "Default")
      (node (ref "J9") (pin "4") (pinfunction "4_4") (pintype "passive"))
      (node (ref "R48") (pin "2") (pinfunction "2_2") (pintype "passive"))
    )
    (net (code "68") (name "Net-(J11-Pad1)") (class "Default")
      (node (ref "J11") (pin "1") (pinfunction "1_1") (pintype "bidirectional"))
      (node (ref "JP3") (pin "2") (pinfunction "2_2") (pintype "passive"))
    )
    (net (code "69") (name "Net-(J11-Pad2)") (class "Default")
      (node (ref "J11") (pin "2") (pinfunction "2_2") (pintype "bidirectional"))
      (node (ref "R14") (pin "2") (pinfunction "2_2") (pintype "passive"))
    )
    (net (code "70") (name "Net-(J11-Pad3)") (class "Default")
      (node (ref "J11") (pin "3") (pinfunction "3_3") (pintype "bidirectional"))
      (node (ref "JP2") (pin "2") (pinfunction "2_2") (pintype "passive"))
      (node (ref "R15") (pin "2") (pinfunction "2_2") (pintype "passive"))
    )
    (net (code "71") (name "Net-(J12-Pad1)") (class "Default")
      (node (ref "J12") (pin "1") (pinfunction "1_1") (pintype "bidirectional"))
      (node (ref "JP6") (pin "2") (pinfunction "2_2") (pintype "passive"))
    )
    (net (code "72") (name "Net-(JP2-Pad1)") (class "Default")
      (node (ref "JP2") (pin "1") (pinfunction "1_1") (pintype "passive"))
      (node (ref "R16") (pin "2") (pinfunction "2_2") (pintype "passive"))
    )
    (net (code "73") (name "Net-(JP4-Pad2)") (class "Default")
      (node (ref "JP4") (pin "2") (pinfunction "2_2") (pintype "passive"))
      (node (ref "R10") (pin "2") (pinfunction "2_2") (pintype "passive"))
      (node (ref "R7") (pin "2") (pinfunction "2_2") (pintype "passive"))
      (node (ref "R8") (pin "2") (pinfunction "2_2") (pintype "passive"))
      (node (ref "R9") (pin "2") (pinfunction "2_2") (pintype "passive"))
    )
    (net (code "74") (name "Net-(Q1-G)") (class "Default")
      (node (ref "Q1") (pin "1") (pinfunction "G_1") (pintype "bidirectional"))
      (node (ref "R38") (pin "1") (pinfunction "1_1") (pintype "passive"))
      (node (ref "R39") (pin "2") (pinfunction "2_2") (pintype "passive"))
    )
    (net (code "75") (name "Net-(Q2-G)") (class "Default")
      (node (ref "Q2") (pin "1") (pinfunction "G_1") (pintype "bidirectional"))
      (node (ref "R36") (pin "1") (pinfunction "1_1") (pintype "passive"))
      (node (ref "R37") (pin "2") (pinfunction "2_2") (pintype "passive"))
    )
    (net (code "76") (name "Net-(Q3-E)") (class "Default")
      (node (ref "Q3") (pin "1") (pinfunction "E_1") (pintype "bidirectional"))
      (node (ref "R37") (pin "1") (pinfunction "1_1") (pintype "passive"))
    )
    (net (code "77") (name "Net-(Q4-E)") (class "Default")
      (node (ref "Q4") (pin "1") (pinfunction "E_1") (pintype "bidirectional"))
      (node (ref "R39") (pin "1") (pinfunction "1_1") (pintype "passive"))
    )
    (net (code "78") (name "Net-(R5-Pad1)") (class "Default")
      (node (ref "R5") (pin "1") (pinfunction "1_1") (pintype "passive"))
      (node (ref "R6") (pin "2") (pinfunction "2_2") (pintype "passive"))
    )
    (net (code "79") (name "Net-(U1-PC14-OSC32_IN)") (class "Default")
      (node (ref "U1") (pin "3") (pinfunction "PC14-OSC32_IN_3") (pintype "bidirectional"))
      (node (ref "Y1") (pin "2") (pinfunction "2_2") (pintype "bidirectional"))
    )
    (net (code "80") (name "Net-(U1-PC15-OSC32_OUT)") (class "Default")
      (node (ref "U1") (pin "4") (pinfunction "PC15-OSC32_OUT_4") (pintype "bidirectional"))
      (node (ref "Y1") (pin "1") (pinfunction "1_1") (pintype "bidirectional"))
    )
    (net (code "81") (name "Net-(U3-+RG)") (class "Default")
      (node (ref "R35") (pin "1") (pinfunction "1_1") (pintype "passive"))
      (node (ref "U3") (pin "8") (pinfunction "+RG_8") (pintype "passive"))
    )
    (net (code "82") (name "Net-(U3--RG)") (class "Default")
      (node (ref "R35") (pin "2") (pinfunction "2_2") (pintype "passive"))
      (node (ref "U3") (pin "1") (pinfunction "-RG_1") (pintype "passive"))
    )
    (net (code "83") (name "Net-(U6-ADJUST)") (class "Default")
      (node (ref "R4") (pin "1") (pinfunction "1_1") (pintype "passive"))
      (node (ref "R5") (pin "2") (pinfunction "2_2") (pintype "passive"))
      (node (ref "U6") (pin "1") (pinfunction "ADJUST_1") (pintype "input"))
    )
    (net (code "84") (name "Net-(U9A-IN1+)") (class "Default")
      (node (ref "R19") (pin "2") (pinfunction "2_2") (pintype "passive"))
      (node (ref "R20") (pin "1") (pinfunction "1_1") (pintype "passive"))
      (node (ref "U9") (pin "3") (pinfunction "IN1+_3") (pintype "input"))
    )
    (net (code "85") (name "Net-(U9A-IN1-)") (class "Default")
      (node (ref "R17") (pin "1") (pinfunction "1_1") (pintype "passive"))
      (node (ref "R18") (pin "2") (pinfunction "2_2") (pintype "passive"))
      (node (ref "U9") (pin "2") (pinfunction "IN1-_2") (pintype "input"))
    )
    (net (code "86") (name "Net-(U9B-IN2+)") (class "Default")
      (node (ref "R23") (pin "1") (pinfunction "1_1") (pintype "passive"))
      (node (ref "R24") (pin "1") (pinfunction "1_1") (pintype "passive"))
      (node (ref "U9") (pin "5") (pinfunction "IN2+_5") (pintype "input"))
    )
    (net (code "87") (name "Net-(U9B-IN2-)") (class "Default")
      (node (ref "R21") (pin "1") (pinfunction "1_1") (pintype "passive"))
      (node (ref "R22") (pin "2") (pinfunction "2_2") (pintype "passive"))
      (node (ref "U9") (pin "6") (pinfunction "IN2-_6") (pintype "input"))
    )
    (net (code "88") (name "Net-(U9C-IN3+)") (class "Default")
      (node (ref "R27") (pin "2") (pinfunction "2_2") (pintype "passive"))
      (node (ref "R28") (pin "1") (pinfunction "1_1") (pintype "passive"))
      (node (ref "U9") (pin "10") (pinfunction "IN3+_10") (pintype "input"))
    )
    (net (code "89") (name "Net-(U9C-IN3-)") (class "Default")
      (node (ref "R25") (pin "1") (pinfunction "1_1") (pintype "passive"))
      (node (ref "R26") (pin "2") (pinfunction "2_2") (pintype "passive"))
      (node (ref "U9") (pin "9") (pinfunction "IN3-_9") (pintype "input"))
    )
    (net (code "90") (name "Net-(U9D-IN4+)") (class "Default")
      (node (ref "R31") (pin "2") (pinfunction "2_2") (pintype "passive"))
      (node (ref "R32") (pin "1") (pinfunction "1_1") (pintype "passive"))
      (node (ref "U9") (pin "12") (pinfunction "IN4+_12") (pintype "input"))
    )
    (net (code "91") (name "Net-(U9D-IN4-)") (class "Default")
      (node (ref "R29") (pin "1") (pinfunction "1_1") (pintype "passive"))
      (node (ref "R30") (pin "2") (pinfunction "2_2") (pintype "passive"))
      (node (ref "U9") (pin "13") (pinfunction "IN4-_13") (pintype "input"))
    )
    (net (code "92") (name "Net-(U10A-IN1+)") (class "Default")
      (node (ref "C2") (pin "2") (pinfunction "2_2") (pintype "passive"))
      (node (ref "C3") (pin "1") (pinfunction "1_1") (pintype "passive"))
      (node (ref "R33") (pin "2") (pinfunction "2_2") (pintype "passive"))
      (node (ref "R34") (pin "1") (pinfunction "1_1") (pintype "passive"))
      (node (ref "U10") (pin "3") (pinfunction "IN1+_3") (pintype "input"))
    )
    (net (code "93") (name "Net-(U11-AREF)") (class "Default")
      (node (ref "C8") (pin "1") (pinfunction "1_1") (pintype "passive"))
      (node (ref "U11") (pin "20") (pinfunction "AREF_20") (pintype "input"))
    )
    (net (code "94") (name "Net-(U15-DTR)") (class "Default")
      (node (ref "C9") (pin "2") (pinfunction "2_2") (pintype "passive"))
      (node (ref "U15") (pin "2") (pinfunction "DTR_2") (pintype "output"))
    )
    (net (code "95") (name "Net-(U15-USBDM)") (class "Default")
      (node (ref "J12") (pin "2") (pinfunction "2_2") (pintype "bidirectional"))
      (node (ref "U15") (pin "16") (pinfunction "USBDM_16") (pintype "bidirectional"))
    )
    (net (code "96") (name "Net-(U15-USBDP)") (class "Default")
      (node (ref "J12") (pin "3") (pinfunction "3_3") (pintype "bidirectional"))
      (node (ref "U15") (pin "15") (pinfunction "USBDP_15") (pintype "bidirectional"))
    )
    (net (code "97") (name "unconnected-(H1-Pad1)") (class "Default")
      (node (ref "H1") (pin "1") (pinfunction "1_1") (pintype "bidirectional"))
    )
    (net (code "98") (name "unconnected-(H1-Pad2)") (class "Default")
      (node (ref "H1") (pin "2") (pinfunction "2_2") (pintype "bidirectional"))
    )
    (net (code "99") (name "unconnected-(H2-Pad1)") (class "Default")
      (node (ref "H2") (pin "1") (pinfunction "1_1") (pintype "bidirectional"))
    )
    (net (code "100") (name "unconnected-(H2-Pad2)") (class "Default")
      (node (ref "H2") (pin "2") (pinfunction "2_2") (pintype "bidirectional"))
    )
    (net (code "101") (name "unconnected-(IC1-ADDR-Pad1)") (class "Default")
      (node (ref "IC1") (pin "1") (pinfunction "ADDR_1") (pintype "bidirectional"))
    )
    (net (code "102") (name "unconnected-(IC1-AIN2-Pad6)") (class "Default")
      (node (ref "IC1") (pin "6") (pinfunction "AIN2_6") (pintype "bidirectional"))
    )
    (net (code "103") (name "unconnected-(IC1-AIN3-Pad7)") (class "Default")
      (node (ref "IC1") (pin "7") (pinfunction "AIN3_7") (pintype "bidirectional"))
    )
    (net (code "104") (name "unconnected-(IC1-ALERT{slash}RDY-Pad2)") (class "Default")
      (node (ref "IC1") (pin "2") (pinfunction "ALERT/RDY_2") (pintype "bidirectional"))
    )
    (net (code "105") (name "unconnected-(J8-OBGACK-Pad19)") (class "Default")
      (node (ref "J8") (pin "19") (pinfunction "OBGACK_19") (pintype "passive"))
    )
    (net (code "106") (name "unconnected-(J8-OBGRQ-Pad17)") (class "Default")
      (node (ref "J8") (pin "17") (pinfunction "OBGRQ_17") (pintype "passive"))
    )
    (net (code "107") (name "unconnected-(J8-RTCK-Pad11)") (class "Default")
      (node (ref "J8") (pin "11") (pinfunction "RTCK_11") (pintype "passive"))
    )
    (net (code "108") (name "unconnected-(J10-Pad1)") (class "Default")
      (node (ref "J10") (pin "1") (pinfunction "1_1") (pintype "bidirectional"))
    )
    (net (code "109") (name "unconnected-(J10-Pad2)") (class "Default")
      (node (ref "J10") (pin "2") (pinfunction "2_2") (pintype "bidirectional"))
    )
    (net (code "110") (name "unconnected-(J10-Pad3)") (class "Default")
      (node (ref "J10") (pin "3") (pinfunction "3_3") (pintype "bidirectional"))
    )
    (net (code "111") (name "unconnected-(J10-Pad4)") (class "Default")
      (node (ref "J10") (pin "4") (pinfunction "4_4") (pintype "bidirectional"))
    )
    (net (code "112") (name "unconnected-(JP7-Pad2)") (class "Default")
      (node (ref "JP7") (pin "2") (pinfunction "2_2") (pintype "passive"))
    )
    (net (code "113") (name "unconnected-(U1-PA0_WKUP-Pad10)") (class "Default")
      (node (ref "U1") (pin "10") (pinfunction "PA0_WKUP_10") (pintype "bidirectional"))
    )
    (net (code "114") (name "unconnected-(U1-PA1-Pad11)") (class "Default")
      (node (ref "U1") (pin "11") (pinfunction "PA1_11") (pintype "bidirectional"))
    )
    (net (code "115") (name "unconnected-(U1-PA2-Pad12)") (class "Default")
      (node (ref "U1") (pin "12") (pinfunction "PA2_12") (pintype "bidirectional"))
    )
    (net (code "116") (name "unconnected-(U1-PA3-Pad13)") (class "Default")
      (node (ref "U1") (pin "13") (pinfunction "PA3_13") (pintype "bidirectional"))
    )
    (net (code "117") (name "unconnected-(U1-PA4-Pad14)") (class "Default")
      (node (ref "U1") (pin "14") (pinfunction "PA4_14") (pintype "bidirectional"))
    )
    (net (code "118") (name "unconnected-(U1-PA5-Pad15)") (class "Default")
      (node (ref "U1") (pin "15") (pinfunction "PA5_15") (pintype "bidirectional"))
    )
    (net (code "119") (name "unconnected-(U1-PA8-Pad29)") (class "Default")
      (node (ref "U1") (pin "29") (pinfunction "PA8_29") (pintype "bidirectional"))
    )
    (net (code "120") (name "unconnected-(U1-PB5-Pad41)") (class "Default")
      (node (ref "U1") (pin "41") (pinfunction "PB5_41") (pintype "bidirectional"))
    )
    (net (code "121") (name "unconnected-(U1-PB6-Pad42)") (class "Default")
      (node (ref "U1") (pin "42") (pinfunction "PB6_42") (pintype "bidirectional"))
    )
    (net (code "122") (name "unconnected-(U1-PB7-Pad43)") (class "Default")
      (node (ref "U1") (pin "43") (pinfunction "PB7_43") (pintype "bidirectional"))
    )
    (net (code "123") (name "unconnected-(U1-PB8-Pad45)") (class "Default")
      (node (ref "U1") (pin "45") (pinfunction "PB8_45") (pintype "bidirectional"))
    )
    (net (code "124") (name "unconnected-(U1-PB9-Pad46)") (class "Default")
      (node (ref "U1") (pin "46") (pinfunction "PB9_46") (pintype "bidirectional"))
    )
    (net (code "125") (name "unconnected-(U1-PC13-TAMPER-RTC-Pad2)") (class "Default")
      (node (ref "U1") (pin "2") (pinfunction "PC13-TAMPER-RTC_2") (pintype "bidirectional"))
    )
    (net (code "126") (name "unconnected-(U1-PD0_OSC_IN-Pad5)") (class "Default")
      (node (ref "U1") (pin "5") (pinfunction "PD0_OSC_IN_5") (pintype "bidirectional"))
    )
    (net (code "127") (name "unconnected-(U1-PD1_OSC_OUT-Pad6)") (class "Default")
      (node (ref "U1") (pin "6") (pinfunction "PD1_OSC_OUT_6") (pintype "bidirectional"))
    )
    (net (code "128") (name "unconnected-(U1-VBAT-Pad1)") (class "Default")
      (node (ref "U1") (pin "1") (pinfunction "VBAT_1") (pintype "bidirectional"))
    )
    (net (code "129") (name "unconnected-(U4-Pad2)") (class "Default")
      (node (ref "U4") (pin "2") (pinfunction "2_2") (pintype "bidirectional"))
    )
    (net (code "130") (name "unconnected-(U4-Pad3)") (class "Default")
      (node (ref "U4") (pin "3") (pinfunction "3_3") (pintype "bidirectional"))
    )
    (net (code "131") (name "unconnected-(U5-Pad2)") (class "Default")
      (node (ref "U5") (pin "2") (pinfunction "2_2") (pintype "bidirectional"))
    )
    (net (code "132") (name "unconnected-(U5-Pad3)") (class "Default")
      (node (ref "U5") (pin "3") (pinfunction "3_3") (pintype "bidirectional"))
    )
    (net (code "133") (name "unconnected-(U11-ADC6-Pad19)") (class "Default")
      (node (ref "U11") (pin "19") (pinfunction "ADC6_19") (pintype "bidirectional"))
    )
    (net (code "134") (name "unconnected-(U11-ADC7-Pad22)") (class "Default")
      (node (ref "U11") (pin "22") (pinfunction "ADC7_22") (pintype "bidirectional"))
    )
    (net (code "135") (name "unconnected-(U11-PB0-Pad12)") (class "Default")
      (node (ref "U11") (pin "12") (pinfunction "PB0_12") (pintype "bidirectional"))
    )
    (net (code "136") (name "unconnected-(U11-PB1-Pad13)") (class "Default")
      (node (ref "U11") (pin "13") (pinfunction "PB1_13") (pintype "bidirectional"))
    )
    (net (code "137") (name "unconnected-(U11-PB2-Pad14)") (class "Default")
      (node (ref "U11") (pin "14") (pinfunction "PB2_14") (pintype "bidirectional"))
    )
    (net (code "138") (name "unconnected-(U11-PB6-Pad7)") (class "Default")
      (node (ref "U11") (pin "7") (pinfunction "PB6_7") (pintype "bidirectional"))
    )
    (net (code "139") (name "unconnected-(U11-PB7-Pad8)") (class "Default")
      (node (ref "U11") (pin "8") (pinfunction "PB7_8") (pintype "bidirectional"))
    )
    (net (code "140") (name "unconnected-(U11-PC0-Pad23)") (class "Default")
      (node (ref "U11") (pin "23") (pinfunction "PC0_23") (pintype "bidirectional"))
    )
    (net (code "141") (name "unconnected-(U11-PC1-Pad24)") (class "Default")
      (node (ref "U11") (pin "24") (pinfunction "PC1_24") (pintype "bidirectional"))
    )
    (net (code "142") (name "unconnected-(U11-PC2-Pad25)") (class "Default")
      (node (ref "U11") (pin "25") (pinfunction "PC2_25") (pintype "bidirectional"))
    )
    (net (code "143") (name "unconnected-(U11-PC3-Pad26)") (class "Default")
      (node (ref "U11") (pin "26") (pinfunction "PC3_26") (pintype "bidirectional"))
    )
    (net (code "144") (name "unconnected-(U11-PD2-Pad32)") (class "Default")
      (node (ref "U11") (pin "32") (pinfunction "PD2_32") (pintype "bidirectional"))
    )
    (net (code "145") (name "unconnected-(U11-PD3-Pad1)") (class "Default")
      (node (ref "U11") (pin "1") (pinfunction "PD3_1") (pintype "bidirectional"))
    )
    (net (code "146") (name "unconnected-(U11-PD4-Pad2)") (class "Default")
      (node (ref "U11") (pin "2") (pinfunction "PD4_2") (pintype "bidirectional"))
    )
    (net (code "147") (name "unconnected-(U11-PD7-Pad11)") (class "Default")
      (node (ref "U11") (pin "11") (pinfunction "PD7_11") (pintype "bidirectional"))
    )
    (net (code "148") (name "unconnected-(U15-CTS-Pad11)") (class "Default")
      (node (ref "U15") (pin "11") (pinfunction "CTS_11") (pintype "input"))
    )
    (net (code "149") (name "unconnected-(U15-DCD-Pad10)") (class "Default")
      (node (ref "U15") (pin "10") (pinfunction "DCD_10") (pintype "input"))
    )
    (net (code "150") (name "unconnected-(U15-DSR-Pad9)") (class "Default")
      (node (ref "U15") (pin "9") (pinfunction "DSR_9") (pintype "input"))
    )
    (net (code "151") (name "unconnected-(U15-OSCI-Pad27)") (class "Default")
      (node (ref "U15") (pin "27") (pinfunction "OSCI_27") (pintype "input"))
    )
    (net (code "152") (name "unconnected-(U15-OSCO-Pad28)") (class "Default")
      (node (ref "U15") (pin "28") (pinfunction "OSCO_28") (pintype "output"))
    )
    (net (code "153") (name "unconnected-(U15-PWREN-Pad14)") (class "Default")
      (node (ref "U15") (pin "14") (pinfunction "PWREN_14") (pintype "input"))
    )
    (net (code "154") (name "unconnected-(U15-RI-Pad6)") (class "Default")
      (node (ref "U15") (pin "6") (pinfunction "RI_6") (pintype "input"))
    )
    (net (code "155") (name "unconnected-(U15-RTS-Pad3)") (class "Default")
      (node (ref "U15") (pin "3") (pinfunction "RTS_3") (pintype "output"))
    )
    (net (code "156") (name "unconnected-(U15-RXLED-Pad22)") (class "Default")
      (node (ref "U15") (pin "22") (pinfunction "RXLED_22") (pintype "input"))
    )
    (net (code "157") (name "unconnected-(U15-SLEEP-Pad12)") (class "Default")
      (node (ref "U15") (pin "12") (pinfunction "SLEEP_12") (pintype "input"))
    )
    (net (code "158") (name "unconnected-(U15-TXDEN-Pad13)") (class "Default")
      (node (ref "U15") (pin "13") (pinfunction "TXDEN_13") (pintype "input"))
    )
    (net (code "159") (name "unconnected-(U15-TXLED-Pad23)") (class "Default")
      (node (ref "U15") (pin "23") (pinfunction "TXLED_23") (pintype "input"))
    )
  )
)
